# mediaV3_0.net
KiCad netlist of a schematic drawn in Altium Designer
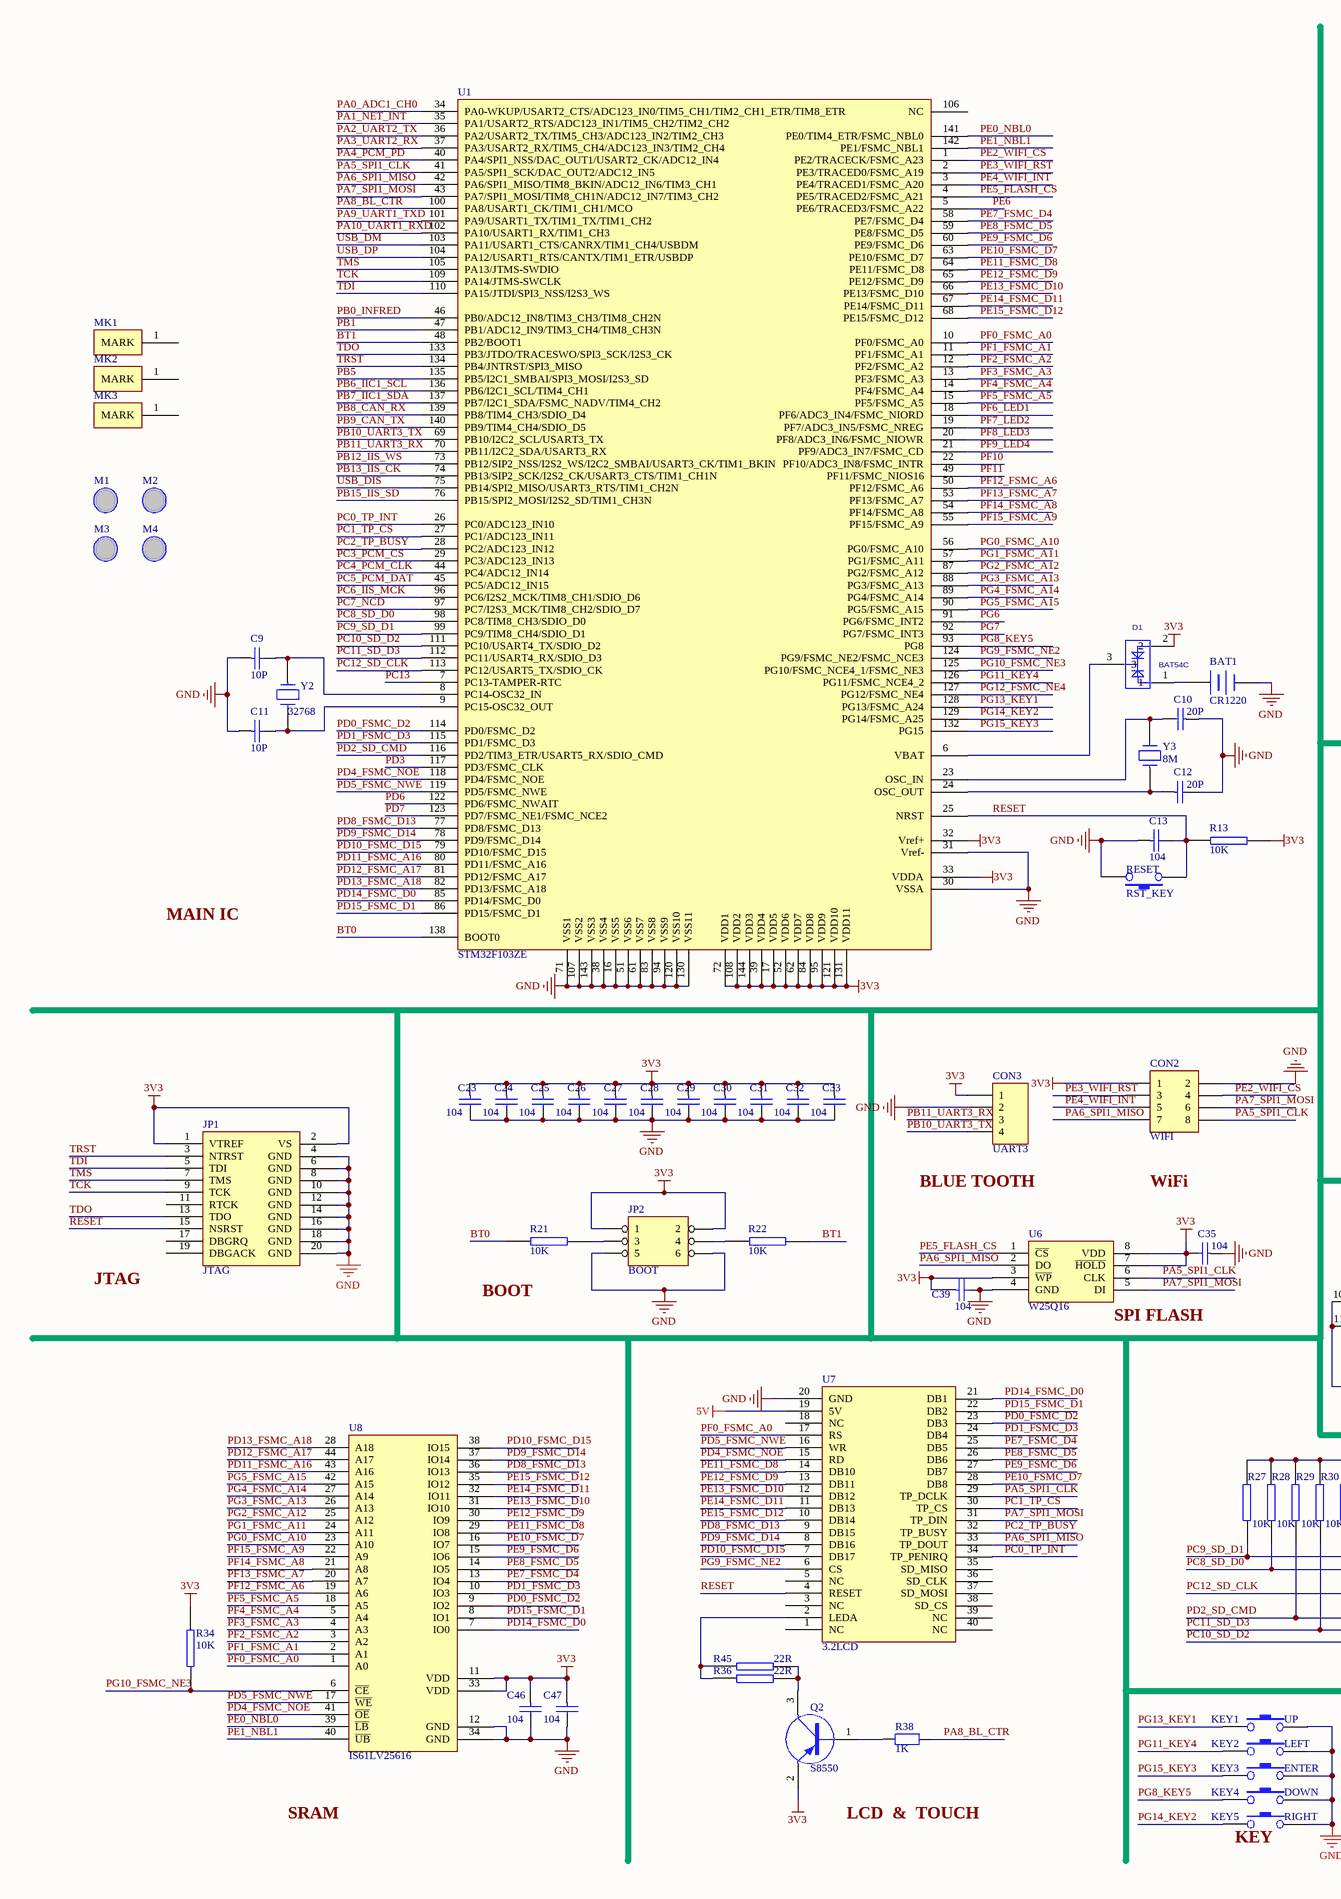
[diagram p0: mediaV3.0.SchDoc, left]
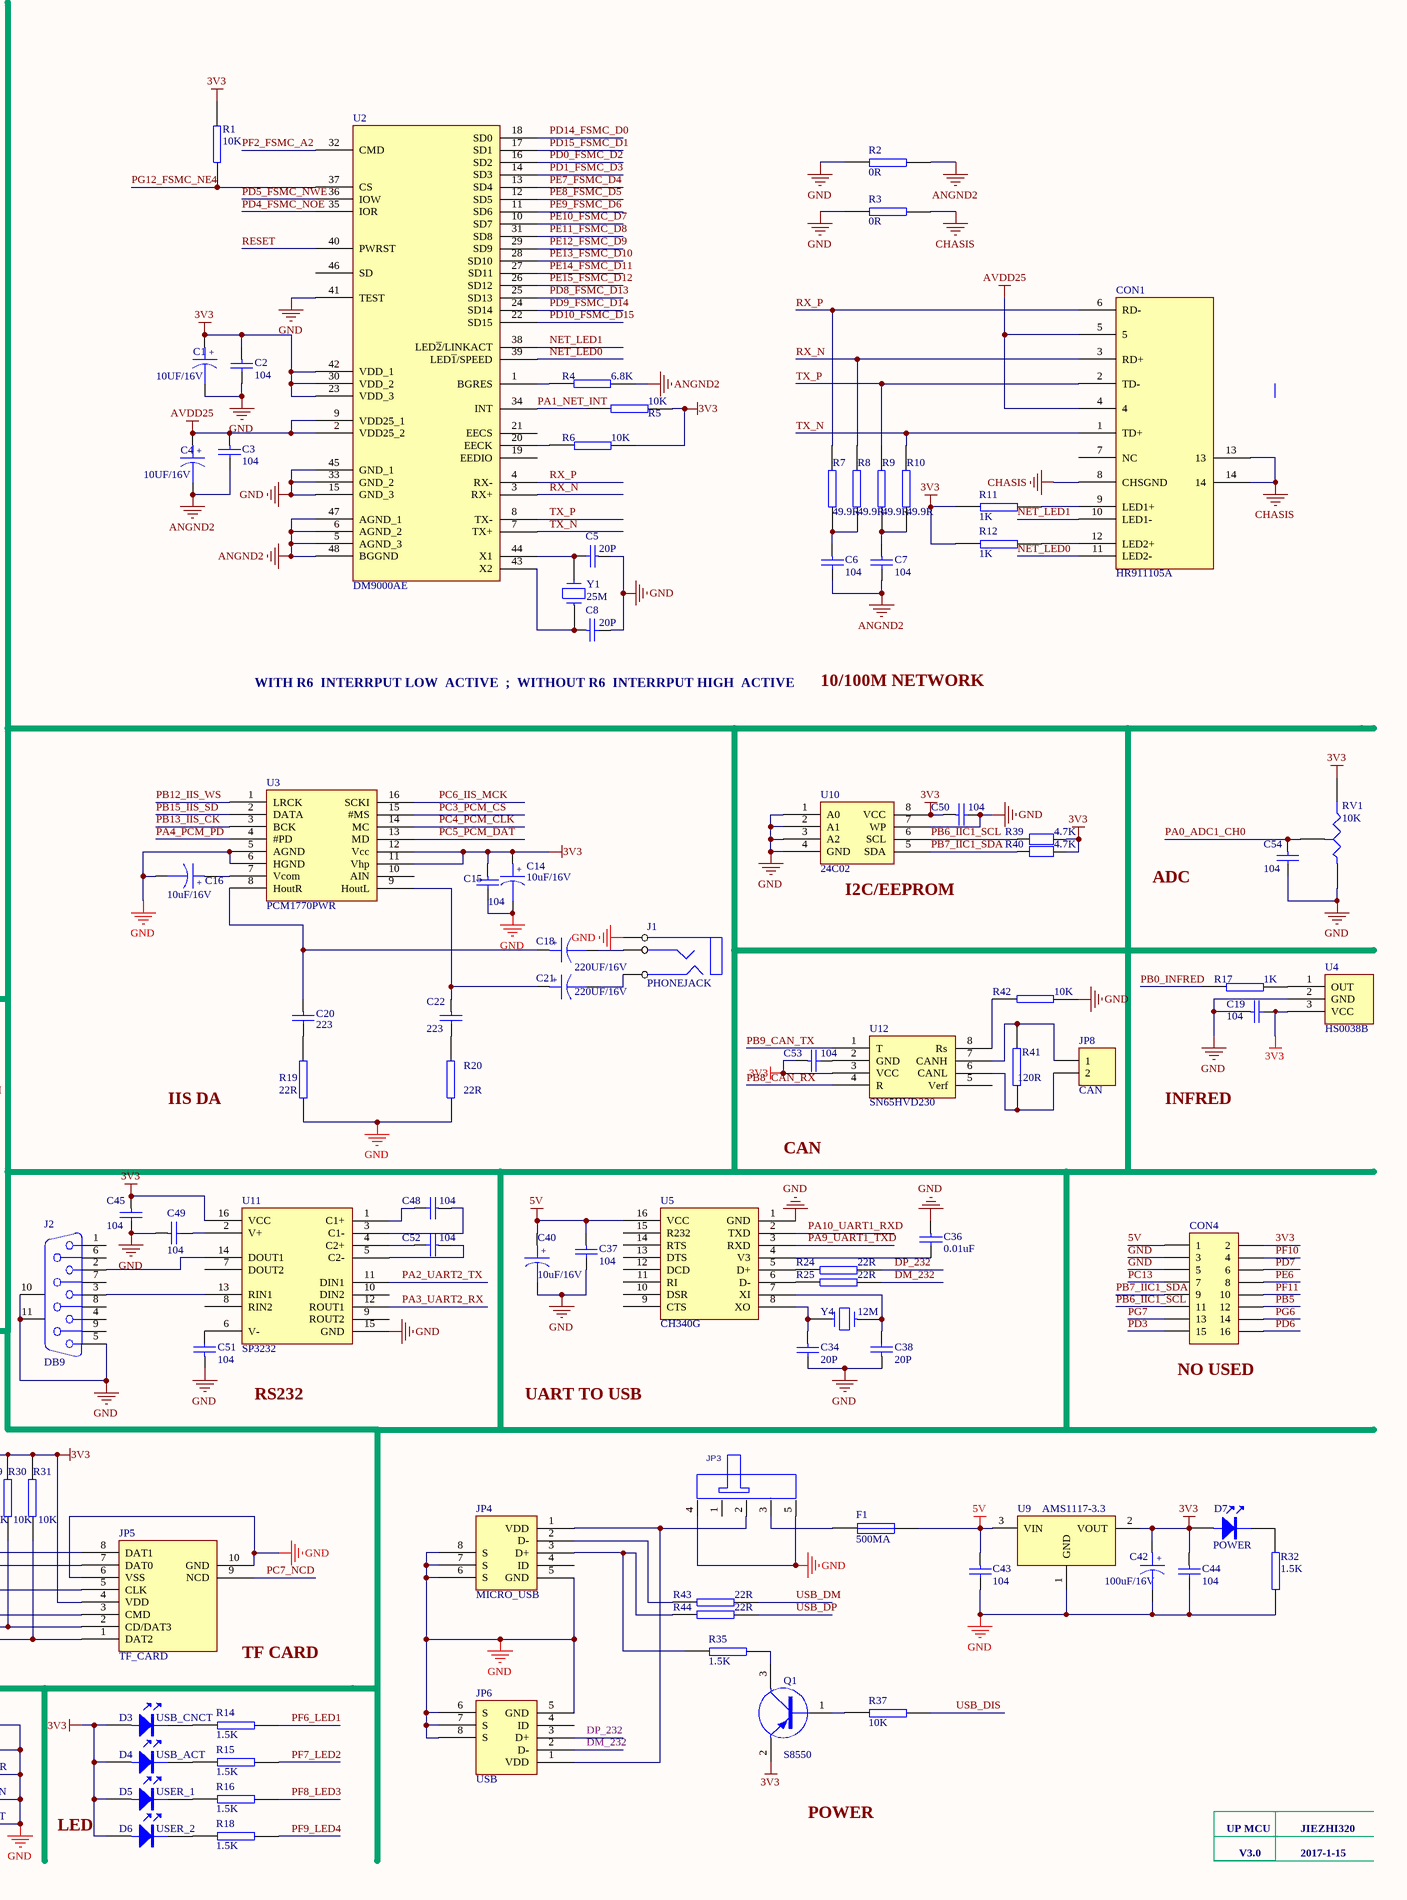
[diagram p1: mediaV3.0.SchDoc, right]

(export (version "E")
  (design (tool "Eeschema 10.0.6"))
  (components
    (comp (ref "BAT1")
      (value "CR1220")
      (footprint "BATM-1220")
      (description "Battery")
      (libsource (lib "Miscellaneous Devices") (part "BATTERY"))
    )
    (comp (ref "C1")
      (value "10UF/16V")
      (footprint "0805C")
      (description "Capacitor")
      (libsource (lib "*") (part "CAPACITOR POL"))
    )
    (comp (ref "C2")
      (value "104")
      (footprint "C0603")
      (description "Capacitor")
      (libsource (lib "*") (part "CAP"))
    )
    (comp (ref "C3")
      (value "104")
      (footprint "C0603")
      (description "Capacitor")
      (libsource (lib "*") (part "CAP"))
    )
    (comp (ref "C4")
      (value "10UF/16V")
      (footprint "0805C")
      (description "Capacitor")
      (libsource (lib "*") (part "CAPACITOR POL"))
    )
    (comp (ref "C5")
      (value "20P")
      (footprint "C0603")
      (description "Capacitor")
      (libsource (lib "*") (part "CAP"))
    )
    (comp (ref "C6")
      (value "104")
      (footprint "C0603")
      (description "Capacitor")
      (libsource (lib "*") (part "CAP"))
    )
    (comp (ref "C7")
      (value "104")
      (footprint "C0603")
      (description "Capacitor")
      (libsource (lib "*") (part "CAP"))
    )
    (comp (ref "C8")
      (value "20P")
      (footprint "C0603")
      (description "Capacitor")
      (libsource (lib "*") (part "CAP"))
    )
    (comp (ref "C9")
      (value "10P")
      (footprint "C0603")
      (description "Capacitor")
      (libsource (lib "*") (part "CAP"))
    )
    (comp (ref "C10")
      (value "20P")
      (footprint "C0603")
      (description "Capacitor")
      (libsource (lib "*") (part "CAP"))
    )
    (comp (ref "C11")
      (value "10P")
      (footprint "C0603")
      (description "Capacitor")
      (libsource (lib "*") (part "CAP"))
    )
    (comp (ref "C12")
      (value "20P")
      (footprint "C0603")
      (description "Capacitor")
      (libsource (lib "*") (part "CAP"))
    )
    (comp (ref "C13")
      (value "104")
      (footprint "C0603")
      (description "Capacitor")
      (libsource (lib "*") (part "CAP"))
    )
    (comp (ref "C14")
      (value "10uF/16V")
      (footprint "0805C")
      (description "Capacitor")
      (libsource (lib "*") (part "CAPACITOR POL"))
    )
    (comp (ref "C15")
      (value "104")
      (footprint "C0603")
      (description "Capacitor")
      (libsource (lib "*") (part "CAP"))
    )
    (comp (ref "C16")
      (value "10uF/16V")
      (footprint "0805C")
      (description "Capacitor")
      (libsource (lib "*") (part "CAPACITOR POL"))
    )
    (comp (ref "C18")
      (value "220UF/16V")
      (footprint "SMD-EC-F6.3")
      (description "Capacitor")
      (libsource (lib "*") (part "CAPACITOR POL"))
    )
    (comp (ref "C19")
      (value "104")
      (footprint "C0603")
      (description "Capacitor")
      (libsource (lib "*") (part "CAP"))
    )
    (comp (ref "C20")
      (value "223")
      (footprint "C0603")
      (description "Capacitor")
      (libsource (lib "*") (part "CAP"))
    )
    (comp (ref "C21")
      (value "220UF/16V")
      (footprint "SMD-EC-F6.3")
      (description "Capacitor")
      (libsource (lib "*") (part "CAPACITOR POL"))
    )
    (comp (ref "C22")
      (value "223")
      (footprint "C0603")
      (description "Capacitor")
      (libsource (lib "*") (part "CAP"))
    )
    (comp (ref "C23")
      (value "104")
      (footprint "C0603")
      (description "Capacitor")
      (libsource (lib "*") (part "CAP"))
    )
    (comp (ref "C24")
      (value "104")
      (footprint "C0603")
      (description "Capacitor")
      (libsource (lib "*") (part "CAP"))
    )
    (comp (ref "C25")
      (value "104")
      (footprint "C0603")
      (description "Capacitor")
      (libsource (lib "*") (part "CAP"))
    )
    (comp (ref "C26")
      (value "104")
      (footprint "C0603")
      (description "Capacitor")
      (libsource (lib "*") (part "CAP"))
    )
    (comp (ref "C27")
      (value "104")
      (footprint "C0603")
      (description "Capacitor")
      (libsource (lib "*") (part "CAP"))
    )
    (comp (ref "C28")
      (value "104")
      (footprint "C0603")
      (description "Capacitor")
      (libsource (lib "*") (part "CAP"))
    )
    (comp (ref "C29")
      (value "104")
      (footprint "C0603")
      (description "Capacitor")
      (libsource (lib "*") (part "CAP"))
    )
    (comp (ref "C30")
      (value "104")
      (footprint "C0603")
      (description "Capacitor")
      (libsource (lib "*") (part "CAP"))
    )
    (comp (ref "C31")
      (value "104")
      (footprint "C0603")
      (description "Capacitor")
      (libsource (lib "*") (part "CAP"))
    )
    (comp (ref "C32")
      (value "104")
      (footprint "C0603")
      (description "Capacitor")
      (libsource (lib "*") (part "CAP"))
    )
    (comp (ref "C33")
      (value "104")
      (footprint "C0603")
      (description "Capacitor")
      (libsource (lib "*") (part "CAP"))
    )
    (comp (ref "C34")
      (value "20P")
      (footprint "C0603")
      (description "Capacitor")
      (libsource (lib "*") (part "CAP"))
    )
    (comp (ref "C35")
      (value "104")
      (footprint "C0603")
      (description "Capacitor")
      (libsource (lib "*") (part "CAP"))
    )
    (comp (ref "C36")
      (value "0.01uF")
      (footprint "C0603")
      (description "Capacitor")
      (libsource (lib "*") (part "CAP"))
    )
    (comp (ref "C37")
      (value "104")
      (footprint "C0603")
      (description "Capacitor")
      (libsource (lib "*") (part "CAP"))
    )
    (comp (ref "C38")
      (value "20P")
      (footprint "C0603")
      (description "Capacitor")
      (libsource (lib "*") (part "CAP"))
    )
    (comp (ref "C39")
      (value "104")
      (footprint "C0603")
      (description "Capacitor")
      (libsource (lib "*") (part "CAP"))
    )
    (comp (ref "C40")
      (value "10uF/16V")
      (footprint "0805C")
      (description "Capacitor")
      (libsource (lib "*") (part "CAPACITOR POL"))
    )
    (comp (ref "C42")
      (value "100uF/16V")
      (footprint "SMD-EC-F6.3")
      (description "Capacitor")
      (libsource (lib "*") (part "CAPACITOR POL"))
    )
    (comp (ref "C43")
      (value "104")
      (footprint "C0603")
      (description "Capacitor")
      (libsource (lib "*") (part "CAP"))
    )
    (comp (ref "C44")
      (value "104")
      (footprint "C0603")
      (description "Capacitor")
      (libsource (lib "*") (part "CAP"))
    )
    (comp (ref "C45")
      (value "104")
      (footprint "C0603")
      (description "Capacitor")
      (libsource (lib "*") (part "CAP"))
    )
    (comp (ref "C46")
      (value "104")
      (footprint "C0603")
      (description "Capacitor")
      (libsource (lib "*") (part "CAP"))
    )
    (comp (ref "C47")
      (value "104")
      (footprint "C0603")
      (description "Capacitor")
      (libsource (lib "*") (part "CAP"))
    )
    (comp (ref "C48")
      (value "104")
      (footprint "C0603")
      (description "Capacitor")
      (libsource (lib "*") (part "CAP"))
    )
    (comp (ref "C49")
      (value "104")
      (footprint "C0603")
      (description "Capacitor")
      (libsource (lib "*") (part "CAP"))
    )
    (comp (ref "C50")
      (value "104")
      (footprint "C0603")
      (description "Capacitor")
      (libsource (lib "*") (part "CAP"))
    )
    (comp (ref "C51")
      (value "104")
      (footprint "C0603")
      (description "Capacitor")
      (libsource (lib "*") (part "CAP"))
    )
    (comp (ref "C52")
      (value "104")
      (footprint "C0603")
      (description "Capacitor")
      (libsource (lib "*") (part "CAP"))
    )
    (comp (ref "C53")
      (value "104")
      (footprint "C0603")
      (description "Capacitor")
      (libsource (lib "*") (part "CAP"))
    )
    (comp (ref "C54")
      (value "104")
      (footprint "C0603")
      (description "Capacitor")
      (libsource (lib "*") (part "CAP"))
    )
    (comp (ref "CON1")
      (value "HR911105A")
      (footprint "CON-HR911105C/RJ45/SC-JL")
      (libsource (lib "*") (part "CN-NET_T/RJ45/HR911105A/HIDE"))
    )
    (comp (ref "CON2")
      (value "WIFI")
      (footprint "WIFI2*4-2.54")
      (description "Header, 4-Pin, Dual row")
      (fields (field (name "PUBLISHER") "Altium Limited"))
      (libsource (lib "Miscellaneous Connectors") (part "Header 4X2"))
    )
    (comp (ref "CON3")
      (value "UART3")
      (footprint "DIP4*1-2.54")
      (description "Header, 4-Pin")
      (fields (field (name "PUBLISHER") "Altium Limited"))
      (libsource (lib "Miscellaneous Connectors") (part "MHDR1X4"))
    )
    (comp (ref "CON4")
      (value "~")
      (footprint "DIP8*2-2.54")
      (description "Header, 8-Pin, Dual row")
      (fields (field (name "PUBLISHER") "Altium Limited"))
      (libsource (lib "Miscellaneous Connectors") (part "Header 8X2"))
    )
    (comp (ref "D1") (value "BAT54C") (footprint "SOT-23") (libsource (lib "F429") (part "BAT54C")))
    (comp (ref "D3")
      (value "USB_CNCT")
      (footprint "D0603")
      (description "POW")
      (libsource (lib "*") (part "LED"))
    )
    (comp (ref "D4") (value "USB_ACT") (footprint "D0603") (libsource (lib "*") (part "LED")))
    (comp (ref "D5") (value "USER_1") (footprint "D0603") (libsource (lib "*") (part "LED")))
    (comp (ref "D6") (value "USER_2") (footprint "D0603") (libsource (lib "*") (part "LED")))
    (comp (ref "D7")
      (value "POWER")
      (footprint "D0603")
      (description "POW")
      (libsource (lib "*") (part "LED"))
    )
    (comp (ref "F1")
      (value "500MA")
      (footprint "R0805")
      (description "Fuse")
      (fields (field (name "PUBLISHER") "Altium Limited"))
      (libsource (lib "Miscellaneous Devices") (part "Fuse 1"))
    )
    (comp (ref "J1")
      (value "PHONEJACK")
      (footprint "PHONE_ST")
      (libsource (lib "*") (part "PHONEJACK STEREO"))
    )
    (comp (ref "J2")
      (value "DB9")
      (footprint "DB-9/FM")
      (description "Receptacle Assembly, 9 Position, Right Angle")
      (fields (field (name "PUBLISHER") "Altium Limited"))
      (libsource (lib "魔笛F4") (part "D Connector 9_Female"))
    )
    (comp (ref "JP1") (value "JTAG") (footprint "JTAG_20") (libsource (lib "*") (part "JTAG")))
    (comp (ref "JP2")
      (value "BOOT")
      (footprint "BOOT_SEL")
      (libsource (lib "Miscellaneous Devices") (part "HEADER 3X2"))
    )
    (comp (ref "JP3")
      (value "SW-POWER")
      (footprint "SW13_6")
      (description "SW-5")
      (libsource (lib "F429") (part "SW-POWER"))
    )
    (comp (ref "JP4")
      (value "MICRO_USB")
      (footprint "USB-MICRO-5P-2 - NJ")
      (libsource (lib "mediaV3.0") (part "MICRO_USB"))
    )
    (comp (ref "JP5") (value "TF_CARD") (footprint "TF-2") (libsource (lib "up-player") (part "TF_CARD")))
    (comp (ref "JP6")
      (value "USB")
      (footprint "USB-MICRO-5P-2 - NJ")
      (libsource (lib "") (part "MICRO_USB_1"))
    )
    (comp (ref "JP8")
      (value "CAN")
      (footprint "CON_2PIN - N")
      (description "Header, 2-Pin")
      (fields (field (name "PUBLISHER") "Altium Limited"))
      (libsource (lib "Miscellaneous Connectors") (part "Header 2"))
    )
    (comp (ref "KEY1") (value "UP") (footprint "KEY4 - SMD") (libsource (lib "*") (part "SW-PB")))
    (comp (ref "KEY2") (value "LEFT") (footprint "KEY4 - SMD") (libsource (lib "*") (part "SW-PB")))
    (comp (ref "KEY3") (value "ENTER") (footprint "KEY4 - SMD") (libsource (lib "*") (part "SW-PB")))
    (comp (ref "KEY4") (value "DOWN") (footprint "KEY4 - SMD") (libsource (lib "*") (part "SW-PB")))
    (comp (ref "KEY5") (value "RIGHT") (footprint "KEY4 - SMD") (libsource (lib "*") (part "SW-PB")))
    (comp (ref "M1") (value "MM") (footprint "PAD") (libsource (lib "mediaV2.1") (part "MM")))
    (comp (ref "M2") (value "MM") (footprint "PAD") (libsource (lib "mediaV2.1") (part "MM")))
    (comp (ref "M3") (value "MM") (footprint "PAD") (libsource (lib "mediaV2.1") (part "MM")))
    (comp (ref "M4") (value "MM") (footprint "PAD") (libsource (lib "mediaV2.1") (part "MM")))
    (comp (ref "MK1") (value "~") (footprint "MARK") (libsource (lib "kevin") (part "MARK")))
    (comp (ref "MK2") (value "~") (footprint "MARK") (libsource (lib "kevin") (part "MARK")))
    (comp (ref "MK3") (value "~") (footprint "MARK") (libsource (lib "kevin") (part "MARK")))
    (comp (ref "Q1")
      (value "S8550")
      (footprint "SOT-23")
      (description "PNP Transistor")
      (libsource (lib "mediaV3.0") (part "PNP"))
    )
    (comp (ref "Q2")
      (value "S8550")
      (footprint "SOT-23")
      (description "PNP Transistor")
      (libsource (lib "mediaV3.0") (part "PNP"))
    )
    (comp (ref "R1") (value "10K") (footprint "R0603") (libsource (lib "*") (part "RES2")))
    (comp (ref "R2") (value "0R") (footprint "R0603") (libsource (lib "*") (part "RES2")))
    (comp (ref "R3") (value "0R") (footprint "R0603") (libsource (lib "*") (part "RES2")))
    (comp (ref "R4") (value "6.8K") (footprint "R0603") (libsource (lib "*") (part "RES2")))
    (comp (ref "R5") (value "10K") (footprint "R0603") (libsource (lib "*") (part "RES2")))
    (comp (ref "R6") (value "10K") (footprint "R0603") (libsource (lib "*") (part "RES2")))
    (comp (ref "R7") (value "49.9R") (footprint "R0603") (libsource (lib "*") (part "RES2")))
    (comp (ref "R8") (value "49.9R") (footprint "R0603") (libsource (lib "*") (part "RES2")))
    (comp (ref "R9") (value "49.9R") (footprint "R0603") (libsource (lib "*") (part "RES2")))
    (comp (ref "R10") (value "49.9R") (footprint "R0603") (libsource (lib "*") (part "RES2")))
    (comp (ref "R11") (value "1K") (footprint "R0603") (libsource (lib "*") (part "RES2")))
    (comp (ref "R12") (value "1K") (footprint "R0603") (libsource (lib "*") (part "RES2")))
    (comp (ref "R13") (value "10K") (footprint "R0603") (libsource (lib "*") (part "RES2")))
    (comp (ref "R14") (value "1.5K") (footprint "R0603") (libsource (lib "*") (part "RES2")))
    (comp (ref "R15") (value "1.5K") (footprint "R0603") (libsource (lib "*") (part "RES2")))
    (comp (ref "R16") (value "1.5K") (footprint "R0603") (libsource (lib "*") (part "RES2")))
    (comp (ref "R17") (value "1K") (footprint "R0603") (libsource (lib "*") (part "RES2")))
    (comp (ref "R18") (value "1.5K") (footprint "R0603") (libsource (lib "*") (part "RES2")))
    (comp (ref "R19") (value "22R") (footprint "R0603") (libsource (lib "*") (part "RES2")))
    (comp (ref "R20") (value "22R") (footprint "R0603") (libsource (lib "*") (part "RES2")))
    (comp (ref "R21") (value "10K") (footprint "R0603") (libsource (lib "*") (part "RES2")))
    (comp (ref "R22") (value "10K") (footprint "R0603") (libsource (lib "*") (part "RES2")))
    (comp (ref "R24") (value "22R") (footprint "R0603") (libsource (lib "*") (part "RES2")))
    (comp (ref "R25") (value "22R") (footprint "R0603") (libsource (lib "*") (part "RES2")))
    (comp (ref "R27") (value "10K") (footprint "R0603") (libsource (lib "*") (part "RES2")))
    (comp (ref "R28") (value "10K") (footprint "R0603") (libsource (lib "*") (part "RES2")))
    (comp (ref "R29") (value "10K") (footprint "R0603") (libsource (lib "*") (part "RES2")))
    (comp (ref "R30") (value "10K") (footprint "R0603") (libsource (lib "*") (part "RES2")))
    (comp (ref "R31") (value "10K") (footprint "R0603") (libsource (lib "*") (part "RES2")))
    (comp (ref "R32") (value "1.5K") (footprint "R0603") (libsource (lib "*") (part "RES2")))
    (comp (ref "R34") (value "10K") (footprint "R0603") (libsource (lib "*") (part "RES2")))
    (comp (ref "R35")
      (value "1.5K")
      (footprint "R0603")
      (libsource (lib "Miscellaneous Devices") (part "RES2"))
    )
    (comp (ref "R36") (value "22R") (footprint "R0603") (libsource (lib "*") (part "RES2")))
    (comp (ref "R37")
      (value "10K")
      (footprint "R0603")
      (libsource (lib "Miscellaneous Devices") (part "RES2"))
    )
    (comp (ref "R38")
      (value "1K")
      (footprint "R0603")
      (description "Resistor")
      (fields (field (name "PUBLISHER") "Altium Limited"))
      (libsource (lib "Miscellaneous Devices") (part "Res2"))
    )
    (comp (ref "R39")
      (value "4.7K")
      (footprint "R0603")
      (description "Resistor")
      (fields (field (name "PUBLISHER") "Altium Limited"))
      (libsource (lib "Miscellaneous Devices") (part "Res2"))
    )
    (comp (ref "R40")
      (value "4.7K")
      (footprint "R0603")
      (description "Resistor")
      (fields (field (name "PUBLISHER") "Altium Limited"))
      (libsource (lib "Miscellaneous Devices") (part "Res2"))
    )
    (comp (ref "R41") (value "120R") (footprint "R0603") (libsource (lib "*") (part "RES2")))
    (comp (ref "R42") (value "10K") (footprint "R0603") (libsource (lib "*") (part "RES2")))
    (comp (ref "R43") (value "22R") (footprint "R0603") (libsource (lib "*") (part "RES2")))
    (comp (ref "R44") (value "22R") (footprint "R0603") (libsource (lib "*") (part "RES2")))
    (comp (ref "R45") (value "22R") (footprint "R0603") (libsource (lib "*") (part "RES2")))
    (comp (ref "RESET") (value "RST_KEY") (footprint "KEY4 - SMD") (libsource (lib "*") (part "SW-PB")))
    (comp (ref "RV1")
      (value "10K")
      (footprint "VR5 - N")
      (libsource (lib "Miscellaneous Devices") (part "RESISTOR TAPPED"))
    )
    (comp (ref "U1")
      (value "STM32F103ZE")
      (footprint "LQFP144-M")
      (libsource (lib "new") (part "STM32F103ZE"))
    )
    (comp (ref "U2")
      (value "DM9000AE")
      (footprint "QFP48")
      (libsource (lib "*") (part "U-DM9000AE/LQFP-48P-Y"))
    )
    (comp (ref "U3") (value "PCM1770PWR") (footprint "TSSOP-16") (libsource (lib "*") (part "PCM1770")))
    (comp (ref "U4") (value "HS0038B") (footprint "HS0038") (libsource (lib "new") (part "INFRED")))
    (comp (ref "U5") (value "CH340G") (footprint "SOP16M") (libsource (lib "Schlib1") (part "CH340G")))
    (comp (ref "U6") (value "W25Q16") (footprint "SOP8") (libsource (lib "mediaV2.1") (part "W25Q16")))
    (comp (ref "U7") (value "3.2LCD") (footprint "LCD") (libsource (lib "media") (part "3.2LCD")))
    (comp (ref "U8") (value "IS61LV25616") (footprint "TSOP44-2") (libsource (lib "*") (part "IS61LV51216")))
    (comp (ref "U9") (value "AMS1117-3.3") (footprint "SOT-223/P2.3") (libsource (lib "*") (part "AMS1117")))
    (comp (ref "U10") (value "24C02") (footprint "SOP-8") (libsource (lib "Schlib1") (part "24C02")))
    (comp (ref "U11") (value "SP3232") (footprint "SOP16M") (libsource (lib "F4") (part "SP3232")))
    (comp (ref "U12")
      (value "SN65HVD230")
      (footprint "SOP-8")
      (libsource (lib "mediaV3.0") (part "SN65HVD230"))
    )
    (comp (ref "Y1")
      (value "25M")
      (footprint "XTAL2")
      (description "Crystal")
      (libsource (lib "*") (part "CRYSTAL"))
    )
    (comp (ref "Y2")
      (value "32768")
      (footprint "XT-32768T")
      (description "Crystal")
      (libsource (lib "*") (part "CRYSTAL"))
    )
    (comp (ref "Y3")
      (value "8M")
      (footprint "XTAL2")
      (description "Crystal")
      (libsource (lib "*") (part "CRYSTAL"))
    )
    (comp (ref "Y4")
      (value "12M")
      (footprint "XTAL2")
      (description "Crystal")
      (libsource (lib "*") (part "CRYSTAL"))
    )
  )
  (nets
    (net (code "2") (name "/BT0") (class "Default")
      (node (ref "R21") (pin "1") (pinfunction "1_1") (pintype "passive"))
      (node (ref "U1") (pin "138") (pinfunction "BOOT0_138") (pintype "passive"))
    )
    (net (code "3") (name "/BT1") (class "Default")
      (node (ref "R22") (pin "2") (pinfunction "2_2") (pintype "passive"))
      (node (ref "U1") (pin "48") (pinfunction "PB2/BOOT1_48") (pintype "passive"))
    )
    (net (code "4") (name "/DM_232") (class "Default")
      (node (ref "JP6") (pin "2") (pinfunction "D-_2") (pintype "passive"))
      (node (ref "R25") (pin "2") (pinfunction "2_2") (pintype "passive"))
    )
    (net (code "5") (name "/DP_232") (class "Default")
      (node (ref "JP6") (pin "3") (pinfunction "D+_3") (pintype "passive"))
      (node (ref "R24") (pin "2") (pinfunction "2_2") (pintype "passive"))
    )
    (net (code "6") (name "/NET_LED0") (class "Default")
      (node (ref "CON1") (pin "11") (pinfunction "LED2-_11") (pintype "passive"))
      (node (ref "U2") (pin "39") (pinfunction "LED~{1}/SPEED_39") (pintype "passive"))
    )
    (net (code "7") (name "/NET_LED1") (class "Default")
      (node (ref "CON1") (pin "10") (pinfunction "LED1-_10") (pintype "passive"))
      (node (ref "U2") (pin "38") (pinfunction "LED~{2}/LINKACT_38") (pintype "passive"))
    )
    (net (code "8") (name "/PA0_ADC1_CH0") (class "Default")
      (node (ref "C54") (pin "1") (pinfunction "1_1") (pintype "passive"))
      (node (ref "RV1") (pin "3") (pinfunction "TAP_3") (pintype "passive"))
      (node (ref "U1") (pin "34") (pinfunction "PA0-WKUP/USART2_CTS/ADC123_IN0/TIM5_CH1/TIM2_CH1_ETR/TIM8_ETR_34") (pintype "passive"))
    )
    (net (code "9") (name "/PA1_NET_INT") (class "Default")
      (node (ref "R5") (pin "1") (pinfunction "1_1") (pintype "passive"))
      (node (ref "U1") (pin "35") (pinfunction "PA1/USART2_RTS/ADC123_IN1/TIM5_CH2/TIM2_CH2_35") (pintype "passive"))
      (node (ref "U2") (pin "34") (pinfunction "INT_34") (pintype "passive"))
    )
    (net (code "10") (name "/PA2_UART2_TX") (class "Default")
      (node (ref "U1") (pin "36") (pinfunction "PA2/USART2_TX/TIM5_CH3/ADC123_IN2/TIM2_CH3_36") (pintype "passive"))
      (node (ref "U11") (pin "11") (pinfunction "DIN1_11") (pintype "passive"))
    )
    (net (code "11") (name "/PA3_UART2_RX") (class "Default")
      (node (ref "U1") (pin "37") (pinfunction "PA3/USART2_RX/TIM5_CH4/ADC123_IN3/TIM2_CH4_37") (pintype "passive"))
      (node (ref "U11") (pin "12") (pinfunction "ROUT1_12") (pintype "passive"))
    )
    (net (code "12") (name "/PA4_PCM_PD") (class "Default")
      (node (ref "U1") (pin "40") (pinfunction "PA4/SPI1_NSS/DAC_OUT1/USART2_CK/ADC12_IN4_40") (pintype "passive"))
      (node (ref "U3") (pin "4") (pinfunction "#PD_4") (pintype "passive"))
    )
    (net (code "13") (name "/PA5_SPI1_CLK") (class "Default")
      (node (ref "CON2") (pin "8") (pinfunction "8_8") (pintype "passive"))
      (node (ref "U1") (pin "41") (pinfunction "PA5/SPI1_SCK/DAC_OUT2/ADC12_IN5_41") (pintype "passive"))
      (node (ref "U6") (pin "6") (pinfunction "CLK_6") (pintype "passive"))
      (node (ref "U7") (pin "29") (pinfunction "TP_DCLK_29") (pintype "passive"))
    )
    (net (code "14") (name "/PA6_SPI1_MISO") (class "Default")
      (node (ref "CON2") (pin "7") (pinfunction "7_7") (pintype "passive"))
      (node (ref "U1") (pin "42") (pinfunction "PA6/SPI1_MISO/TIM8_BKIN/ADC12_IN6/TIM3_CH1_42") (pintype "passive"))
      (node (ref "U6") (pin "2") (pinfunction "DO_2") (pintype "passive"))
      (node (ref "U7") (pin "33") (pinfunction "TP_DOUT_33") (pintype "passive"))
    )
    (net (code "15") (name "/PA7_SPI1_MOSI") (class "Default")
      (node (ref "CON2") (pin "6") (pinfunction "6_6") (pintype "passive"))
      (node (ref "U1") (pin "43") (pinfunction "PA7/SPI1_MOSI/TIM8_CH1N/ADC12_IN7/TIM3_CH2_43") (pintype "passive"))
      (node (ref "U6") (pin "5") (pinfunction "DI_5") (pintype "passive"))
      (node (ref "U7") (pin "31") (pinfunction "TP_DIN_31") (pintype "passive"))
    )
    (net (code "16") (name "/PA8_BL_CTR") (class "Default")
      (node (ref "R38") (pin "2") (pinfunction "2_2") (pintype "passive"))
      (node (ref "U1") (pin "100") (pinfunction "PA8/USART1_CK/TIM1_CH1/MCO_100") (pintype "passive"))
    )
    (net (code "17") (name "/PA9_UART1_TXD") (class "Default")
      (node (ref "U1") (pin "101") (pinfunction "PA9/USART1_TX/TIM1_TX/TIM1_CH2_101") (pintype "passive"))
      (node (ref "U5") (pin "3") (pinfunction "RXD_3") (pintype "passive"))
    )
    (net (code "18") (name "/PA10_UART1_RXD") (class "Default")
      (node (ref "U1") (pin "102") (pinfunction "PA10/USART1_RX/TIM1_CH3_102") (pintype "passive"))
      (node (ref "U5") (pin "2") (pinfunction "TXD_2") (pintype "passive"))
    )
    (net (code "19") (name "/PB0_INFRED") (class "Default")
      (node (ref "R17") (pin "1") (pinfunction "1_1") (pintype "passive"))
      (node (ref "U1") (pin "46") (pinfunction "PB0/ADC12_IN8/TIM3_CH3/TIM8_CH2N_46") (pintype "passive"))
    )
    (net (code "20") (name "/PB1") (class "Default")
      (node (ref "U1") (pin "47") (pinfunction "PB1/ADC12_IN9/TIM3_CH4/TIM8_CH3N_47") (pintype "passive"))
    )
    (net (code "21") (name "/PB5") (class "Default")
      (node (ref "CON4") (pin "12") (pinfunction "12_12") (pintype "passive"))
      (node (ref "U1") (pin "135") (pinfunction "PB5/I2C1_SMBAI/SPI3_MOSI/I2S3_SD_135") (pintype "passive"))
    )
    (net (code "22") (name "/PB6_IIC1_SCL") (class "Default")
      (node (ref "CON4") (pin "11") (pinfunction "11_11") (pintype "passive"))
      (node (ref "R39") (pin "1") (pinfunction "1_1") (pintype "passive"))
      (node (ref "U1") (pin "136") (pinfunction "PB6/I2C1_SCL/TIM4_CH1_136") (pintype "passive"))
      (node (ref "U10") (pin "6") (pinfunction "SCL_6") (pintype "passive"))
    )
    (net (code "23") (name "/PB7_IIC1_SDA") (class "Default")
      (node (ref "CON4") (pin "9") (pinfunction "9_9") (pintype "passive"))
      (node (ref "R40") (pin "1") (pinfunction "1_1") (pintype "passive"))
      (node (ref "U1") (pin "137") (pinfunction "PB7/I2C1_SDA/FSMC_NADV/TIM4_CH2_137") (pintype "passive"))
      (node (ref "U10") (pin "5") (pinfunction "SDA_5") (pintype "passive"))
    )
    (net (code "24") (name "/PB8_CAN_RX") (class "Default")
      (node (ref "U1") (pin "139") (pinfunction "PB8/TIM4_CH3/SDIO_D4_139") (pintype "passive"))
      (node (ref "U12") (pin "4") (pinfunction "R_4") (pintype "passive"))
    )
    (net (code "25") (name "/PB9_CAN_TX") (class "Default")
      (node (ref "U1") (pin "140") (pinfunction "PB9/TIM4_CH4/SDIO_D5_140") (pintype "passive"))
      (node (ref "U12") (pin "1") (pinfunction "T_1") (pintype "passive"))
    )
    (net (code "26") (name "/PB10_UART3_TX") (class "Default")
      (node (ref "CON3") (pin "4") (pinfunction "4_4") (pintype "passive"))
      (node (ref "U1") (pin "69") (pinfunction "PB10/I2C2_SCL/USART3_TX_69") (pintype "passive"))
    )
    (net (code "27") (name "/PB11_UART3_RX") (class "Default")
      (node (ref "CON3") (pin "3") (pinfunction "3_3") (pintype "passive"))
      (node (ref "U1") (pin "70") (pinfunction "PB11/I2C2_SDA/USART3_RX_70") (pintype "passive"))
    )
    (net (code "28") (name "/PB12_IIS_WS") (class "Default")
      (node (ref "U1") (pin "73") (pinfunction "PB12/SIP2_NSS/I2S2_WS/I2C2_SMBAI/USART3_CK/TIM1_BKIN_73") (pintype "passive"))
      (node (ref "U3") (pin "1") (pinfunction "LRCK_1") (pintype "passive"))
    )
    (net (code "29") (name "/PB13_IIS_CK") (class "Default")
      (node (ref "U1") (pin "74") (pinfunction "PB13/SIP2_SCK/I2S2_CK/USART3_CTS/TIM1_CH1N_74") (pintype "passive"))
      (node (ref "U3") (pin "3") (pinfunction "BCK_3") (pintype "passive"))
    )
    (net (code "30") (name "/PB15_IIS_SD") (class "Default")
      (node (ref "U1") (pin "76") (pinfunction "PB15/SPI2_MOSI/I2S2_SD/TIM1_CH3N_76") (pintype "passive"))
      (node (ref "U3") (pin "2") (pinfunction "DATA_2") (pintype "passive"))
    )
    (net (code "31") (name "/PC0_TP_INT") (class "Default")
      (node (ref "U1") (pin "26") (pinfunction "PC0/ADC123_IN10_26") (pintype "passive"))
      (node (ref "U7") (pin "34") (pinfunction "TP_PENIRQ_34") (pintype "passive"))
    )
    (net (code "32") (name "/PC1_TP_CS") (class "Default")
      (node (ref "U1") (pin "27") (pinfunction "PC1/ADC123_IN11_27") (pintype "passive"))
      (node (ref "U7") (pin "30") (pinfunction "TP_CS_30") (pintype "passive"))
    )
    (net (code "33") (name "/PC2_TP_BUSY") (class "Default")
      (node (ref "U1") (pin "28") (pinfunction "PC2/ADC123_IN12_28") (pintype "passive"))
      (node (ref "U7") (pin "32") (pinfunction "TP_BUSY_32") (pintype "passive"))
    )
    (net (code "34") (name "/PC3_PCM_CS") (class "Default")
      (node (ref "U1") (pin "29") (pinfunction "PC3/ADC123_IN13_29") (pintype "passive"))
      (node (ref "U3") (pin "15") (pinfunction "#MS_15") (pintype "passive"))
    )
    (net (code "35") (name "/PC4_PCM_CLK") (class "Default")
      (node (ref "U1") (pin "44") (pinfunction "PC4/ADC12_IN14_44") (pintype "passive"))
      (node (ref "U3") (pin "14") (pinfunction "MC_14") (pintype "passive"))
    )
    (net (code "36") (name "/PC5_PCM_DAT") (class "Default")
      (node (ref "U1") (pin "45") (pinfunction "PC5/ADC12_IN15_45") (pintype "passive"))
      (node (ref "U3") (pin "13") (pinfunction "MD_13") (pintype "passive"))
    )
    (net (code "37") (name "/PC6_IIS_MCK") (class "Default")
      (node (ref "U1") (pin "96") (pinfunction "PC6/I2S2_MCK/TIM8_CH1/SDIO_D6_96") (pintype "passive"))
      (node (ref "U3") (pin "16") (pinfunction "SCKI_16") (pintype "passive"))
    )
    (net (code "38") (name "/PC7_NCD") (class "Default")
      (node (ref "JP5") (pin "9") (pinfunction "NCD_9") (pintype "passive"))
      (node (ref "U1") (pin "97") (pinfunction "PC7/I2S3_MCK/TIM8_CH2/SDIO_D7_97") (pintype "passive"))
    )
    (net (code "39") (name "/PC8_SD_D0") (class "Default")
      (node (ref "JP5") (pin "7") (pinfunction "DAT0_7") (pintype "passive"))
      (node (ref "R28") (pin "1") (pinfunction "1_1") (pintype "passive"))
      (node (ref "U1") (pin "98") (pinfunction "PC8/TIM8_CH3/SDIO_D0_98") (pintype "passive"))
    )
    (net (code "40") (name "/PC9_SD_D1") (class "Default")
      (node (ref "JP5") (pin "8") (pinfunction "DAT1_8") (pintype "passive"))
      (node (ref "R27") (pin "1") (pinfunction "1_1") (pintype "passive"))
      (node (ref "U1") (pin "99") (pinfunction "PC9/TIM8_CH4/SDIO_D1_99") (pintype "passive"))
    )
    (net (code "41") (name "/PC10_SD_D2") (class "Default")
      (node (ref "JP5") (pin "1") (pinfunction "DAT2_1") (pintype "passive"))
      (node (ref "R31") (pin "1") (pinfunction "1_1") (pintype "passive"))
      (node (ref "U1") (pin "111") (pinfunction "PC10/USART4_TX/SDIO_D2_111") (pintype "passive"))
    )
    (net (code "42") (name "/PC11_SD_D3") (class "Default")
      (node (ref "JP5") (pin "2") (pinfunction "CD/DAT3_2") (pintype "passive"))
      (node (ref "R30") (pin "1") (pinfunction "1_1") (pintype "passive"))
      (node (ref "U1") (pin "112") (pinfunction "PC11/USART4_RX/SDIO_D3_112") (pintype "passive"))
    )
    (net (code "43") (name "/PC12_SD_CLK") (class "Default")
      (node (ref "JP5") (pin "5") (pinfunction "CLK_5") (pintype "passive"))
      (node (ref "U1") (pin "113") (pinfunction "PC12/USART5_TX/SDIO_CK_113") (pintype "passive"))
    )
    (net (code "44") (name "/PC13") (class "Default")
      (node (ref "CON4") (pin "7") (pinfunction "7_7") (pintype "passive"))
      (node (ref "U1") (pin "7") (pinfunction "PC13-TAMPER-RTC_7") (pintype "passive"))
    )
    (net (code "45") (name "/PD0_FSMC_D2") (class "Default")
      (node (ref "U1") (pin "114") (pinfunction "PD0/FSMC_D2_114") (pintype "passive"))
      (node (ref "U2") (pin "16") (pinfunction "SD2_16") (pintype "passive"))
      (node (ref "U7") (pin "23") (pinfunction "DB3_23") (pintype "passive"))
      (node (ref "U8") (pin "9") (pinfunction "IO2_9") (pintype "passive"))
    )
    (net (code "46") (name "/PD1_FSMC_D3") (class "Default")
      (node (ref "U1") (pin "115") (pinfunction "PD1/FSMC_D3_115") (pintype "passive"))
      (node (ref "U2") (pin "14") (pinfunction "SD3_14") (pintype "passive"))
      (node (ref "U7") (pin "24") (pinfunction "DB4_24") (pintype "passive"))
      (node (ref "U8") (pin "10") (pinfunction "IO3_10") (pintype "passive"))
    )
    (net (code "47") (name "/PD2_SD_CMD") (class "Default")
      (node (ref "JP5") (pin "3") (pinfunction "CMD_3") (pintype "passive"))
      (node (ref "R29") (pin "1") (pinfunction "1_1") (pintype "passive"))
      (node (ref "U1") (pin "116") (pinfunction "PD2/TIM3_ETR/USART5_RX/SDIO_CMD_116") (pintype "passive"))
    )
    (net (code "48") (name "/PD3") (class "Default")
      (node (ref "CON4") (pin "15") (pinfunction "15_15") (pintype "passive"))
      (node (ref "U1") (pin "117") (pinfunction "PD3/FSMC_CLK_117") (pintype "passive"))
    )
    (net (code "49") (name "/PD4_FSMC_NOE") (class "Default")
      (node (ref "U1") (pin "118") (pinfunction "PD4/FSMC_NOE_118") (pintype "passive"))
      (node (ref "U2") (pin "35") (pinfunction "IOR_35") (pintype "passive"))
      (node (ref "U7") (pin "15") (pinfunction "RD_15") (pintype "passive"))
      (node (ref "U8") (pin "41") (pinfunction "~{OE}_41") (pintype "passive"))
    )
    (net (code "50") (name "/PD5_FSMC_NWE") (class "Default")
      (node (ref "U1") (pin "119") (pinfunction "PD5/FSMC_NWE_119") (pintype "passive"))
      (node (ref "U2") (pin "36") (pinfunction "IOW_36") (pintype "passive"))
      (node (ref "U7") (pin "16") (pinfunction "WR_16") (pintype "passive"))
      (node (ref "U8") (pin "17") (pinfunction "~{WE}_17") (pintype "passive"))
    )
    (net (code "51") (name "/PD6") (class "Default")
      (node (ref "CON4") (pin "16") (pinfunction "16_16") (pintype "passive"))
      (node (ref "U1") (pin "122") (pinfunction "PD6/FSMC_NWAIT_122") (pintype "passive"))
    )
    (net (code "52") (name "/PD7") (class "Default")
      (node (ref "CON4") (pin "6") (pinfunction "6_6") (pintype "passive"))
      (node (ref "U1") (pin "123") (pinfunction "PD7/FSMC_NE1/FSMC_NCE2_123") (pintype "passive"))
    )
    (net (code "53") (name "/PD8_FSMC_D13") (class "Default")
      (node (ref "U1") (pin "77") (pinfunction "PD8/FSMC_D13_77") (pintype "passive"))
      (node (ref "U2") (pin "25") (pinfunction "SD13_25") (pintype "passive"))
      (node (ref "U7") (pin "9") (pinfunction "DB15_9") (pintype "passive"))
      (node (ref "U8") (pin "36") (pinfunction "IO13_36") (pintype "passive"))
    )
    (net (code "54") (name "/PD9_FSMC_D14") (class "Default")
      (node (ref "U1") (pin "78") (pinfunction "PD9/FSMC_D14_78") (pintype "passive"))
      (node (ref "U2") (pin "24") (pinfunction "SD14_24") (pintype "passive"))
      (node (ref "U7") (pin "8") (pinfunction "DB16_8") (pintype "passive"))
      (node (ref "U8") (pin "37") (pinfunction "IO14_37") (pintype "passive"))
    )
    (net (code "55") (name "/PD10_FSMC_D15") (class "Default")
      (node (ref "U1") (pin "79") (pinfunction "PD10/FSMC_D15_79") (pintype "passive"))
      (node (ref "U2") (pin "22") (pinfunction "SD15_22") (pintype "passive"))
      (node (ref "U7") (pin "7") (pinfunction "DB17_7") (pintype "passive"))
      (node (ref "U8") (pin "38") (pinfunction "IO15_38") (pintype "passive"))
    )
    (net (code "56") (name "/PD11_FSMC_A16") (class "Default")
      (node (ref "U1") (pin "80") (pinfunction "PD11/FSMC_A16_80") (pintype "passive"))
      (node (ref "U8") (pin "43") (pinfunction "A16_43") (pintype "passive"))
    )
    (net (code "57") (name "/PD12_FSMC_A17") (class "Default")
      (node (ref "U1") (pin "81") (pinfunction "PD12/FSMC_A17_81") (pintype "passive"))
      (node (ref "U8") (pin "44") (pinfunction "A17_44") (pintype "passive"))
    )
    (net (code "58") (name "/PD13_FSMC_A18") (class "Default")
      (node (ref "U1") (pin "82") (pinfunction "PD13/FSMC_A18_82") (pintype "passive"))
      (node (ref "U8") (pin "28") (pinfunction "A18_28") (pintype "passive"))
    )
    (net (code "59") (name "/PD14_FSMC_D0") (class "Default")
      (node (ref "U1") (pin "85") (pinfunction "PD14/FSMC_D0_85") (pintype "passive"))
      (node (ref "U2") (pin "18") (pinfunction "SD0_18") (pintype "passive"))
      (node (ref "U7") (pin "21") (pinfunction "DB1_21") (pintype "passive"))
      (node (ref "U8") (pin "7") (pinfunction "IO0_7") (pintype "passive"))
    )
    (net (code "60") (name "/PD15_FSMC_D1") (class "Default")
      (node (ref "U1") (pin "86") (pinfunction "PD15/FSMC_D1_86") (pintype "passive"))
      (node (ref "U2") (pin "17") (pinfunction "SD1_17") (pintype "passive"))
      (node (ref "U7") (pin "22") (pinfunction "DB2_22") (pintype "passive"))
      (node (ref "U8") (pin "8") (pinfunction "IO1_8") (pintype "passive"))
    )
    (net (code "61") (name "/PE0_NBL0") (class "Default")
      (node (ref "U1") (pin "141") (pinfunction "PE0/TIM4_ETR/FSMC_NBL0_141") (pintype "passive"))
      (node (ref "U8") (pin "39") (pinfunction "~{LB}_39") (pintype "passive"))
    )
    (net (code "62") (name "/PE1_NBL1") (class "Default")
      (node (ref "U1") (pin "142") (pinfunction "PE1/FSMC_NBL1_142") (pintype "passive"))
      (node (ref "U8") (pin "40") (pinfunction "~{UB}_40") (pintype "passive"))
    )
    (net (code "63") (name "/PE2_WIFI_CS") (class "Default")
      (node (ref "CON2") (pin "4") (pinfunction "4_4") (pintype "passive"))
      (node (ref "U1") (pin "1") (pinfunction "PE2/TRACECK/FSMC_A23_1") (pintype "passive"))
    )
    (net (code "64") (name "/PE3_WIFI_RST") (class "Default")
      (node (ref "CON2") (pin "3") (pinfunction "3_3") (pintype "passive"))
      (node (ref "U1") (pin "2") (pinfunction "PE3/TRACED0/FSMC_A19_2") (pintype "passive"))
    )
    (net (code "65") (name "/PE4_WIFI_INT") (class "Default")
      (node (ref "CON2") (pin "5") (pinfunction "5_5") (pintype "passive"))
      (node (ref "U1") (pin "3") (pinfunction "PE4/TRACED1/FSMC_A20_3") (pintype "passive"))
    )
    (net (code "66") (name "/PE5_FLASH_CS") (class "Default")
      (node (ref "U1") (pin "4") (pinfunction "PE5/TRACED2/FSMC_A21_4") (pintype "passive"))
      (node (ref "U6") (pin "1") (pinfunction "~{CS}_1") (pintype "passive"))
    )
    (net (code "67") (name "/PE6") (class "Default")
      (node (ref "CON4") (pin "8") (pinfunction "8_8") (pintype "passive"))
      (node (ref "U1") (pin "5") (pinfunction "PE6/TRACED3/FSMC_A22_5") (pintype "passive"))
    )
    (net (code "68") (name "/PE7_FSMC_D4") (class "Default")
      (node (ref "U1") (pin "58") (pinfunction "PE7/FSMC_D4_58") (pintype "passive"))
      (node (ref "U2") (pin "13") (pinfunction "SD4_13") (pintype "passive"))
      (node (ref "U7") (pin "25") (pinfunction "DB5_25") (pintype "passive"))
      (node (ref "U8") (pin "13") (pinfunction "IO4_13") (pintype "passive"))
    )
    (net (code "69") (name "/PE8_FSMC_D5") (class "Default")
      (node (ref "U1") (pin "59") (pinfunction "PE8/FSMC_D5_59") (pintype "passive"))
      (node (ref "U2") (pin "12") (pinfunction "SD5_12") (pintype "passive"))
      (node (ref "U7") (pin "26") (pinfunction "DB6_26") (pintype "passive"))
      (node (ref "U8") (pin "14") (pinfunction "IO5_14") (pintype "passive"))
    )
    (net (code "70") (name "/PE9_FSMC_D6") (class "Default")
      (node (ref "U1") (pin "60") (pinfunction "PE9/FSMC_D6_60") (pintype "passive"))
      (node (ref "U2") (pin "11") (pinfunction "SD6_11") (pintype "passive"))
      (node (ref "U7") (pin "27") (pinfunction "DB7_27") (pintype "passive"))
      (node (ref "U8") (pin "15") (pinfunction "IO6_15") (pintype "passive"))
    )
    (net (code "71") (name "/PE10_FSMC_D7") (class "Default")
      (node (ref "U1") (pin "63") (pinfunction "PE10/FSMC_D7_63") (pintype "passive"))
      (node (ref "U2") (pin "10") (pinfunction "SD7_10") (pintype "passive"))
      (node (ref "U7") (pin "28") (pinfunction "DB8_28") (pintype "passive"))
      (node (ref "U8") (pin "16") (pinfunction "IO7_16") (pintype "passive"))
    )
    (net (code "72") (name "/PE11_FSMC_D8") (class "Default")
      (node (ref "U1") (pin "64") (pinfunction "PE11/FSMC_D8_64") (pintype "passive"))
      (node (ref "U2") (pin "31") (pinfunction "SD8_31") (pintype "passive"))
      (node (ref "U7") (pin "14") (pinfunction "DB10_14") (pintype "passive"))
      (node (ref "U8") (pin "29") (pinfunction "IO8_29") (pintype "passive"))
    )
    (net (code "73") (name "/PE12_FSMC_D9") (class "Default")
      (node (ref "U1") (pin "65") (pinfunction "PE12/FSMC_D9_65") (pintype "passive"))
      (node (ref "U2") (pin "29") (pinfunction "SD9_29") (pintype "passive"))
      (node (ref "U7") (pin "13") (pinfunction "DB11_13") (pintype "passive"))
      (node (ref "U8") (pin "30") (pinfunction "IO9_30") (pintype "passive"))
    )
    (net (code "74") (name "/PE13_FSMC_D10") (class "Default")
      (node (ref "U1") (pin "66") (pinfunction "PE13/FSMC_D10_66") (pintype "passive"))
      (node (ref "U2") (pin "28") (pinfunction "SD10_28") (pintype "passive"))
      (node (ref "U7") (pin "12") (pinfunction "DB12_12") (pintype "passive"))
      (node (ref "U8") (pin "31") (pinfunction "IO10_31") (pintype "passive"))
    )
    (net (code "75") (name "/PE14_FSMC_D11") (class "Default")
      (node (ref "U1") (pin "67") (pinfunction "PE14/FSMC_D11_67") (pintype "passive"))
      (node (ref "U2") (pin "27") (pinfunction "SD11_27") (pintype "passive"))
      (node (ref "U7") (pin "11") (pinfunction "DB13_11") (pintype "passive"))
      (node (ref "U8") (pin "32") (pinfunction "IO11_32") (pintype "passive"))
    )
    (net (code "76") (name "/PE15_FSMC_D12") (class "Default")
      (node (ref "U1") (pin "68") (pinfunction "PE15/FSMC_D12_68") (pintype "passive"))
      (node (ref "U2") (pin "26") (pinfunction "SD12_26") (pintype "passive"))
      (node (ref "U7") (pin "10") (pinfunction "DB14_10") (pintype "passive"))
      (node (ref "U8") (pin "35") (pinfunction "IO12_35") (pintype "passive"))
    )
    (net (code "77") (name "/PF0_FSMC_A0") (class "Default")
      (node (ref "U1") (pin "10") (pinfunction "PF0/FSMC_A0_10") (pintype "passive"))
      (node (ref "U7") (pin "17") (pinfunction "RS_17") (pintype "passive"))
      (node (ref "U8") (pin "1") (pinfunction "A0_1") (pintype "passive"))
    )
    (net (code "78") (name "/PF1_FSMC_A1") (class "Default")
      (node (ref "U1") (pin "11") (pinfunction "PF1/FSMC_A1_11") (pintype "passive"))
      (node (ref "U8") (pin "2") (pinfunction "A1_2") (pintype "passive"))
    )
    (net (code "79") (name "/PF2_FSMC_A2") (class "Default")
      (node (ref "U1") (pin "12") (pinfunction "PF2/FSMC_A2_12") (pintype "passive"))
      (node (ref "U2") (pin "32") (pinfunction "CMD_32") (pintype "passive"))
      (node (ref "U8") (pin "3") (pinfunction "A2_3") (pintype "passive"))
    )
    (net (code "80") (name "/PF3_FSMC_A3") (class "Default")
      (node (ref "U1") (pin "13") (pinfunction "PF3/FSMC_A3_13") (pintype "passive"))
      (node (ref "U8") (pin "4") (pinfunction "A3_4") (pintype "passive"))
    )
    (net (code "81") (name "/PF4_FSMC_A4") (class "Default")
      (node (ref "U1") (pin "14") (pinfunction "PF4/FSMC_A4_14") (pintype "passive"))
      (node (ref "U8") (pin "5") (pinfunction "A4_5") (pintype "passive"))
    )
    (net (code "82") (name "/PF5_FSMC_A5") (class "Default")
      (node (ref "U1") (pin "15") (pinfunction "PF5/FSMC_A5_15") (pintype "passive"))
      (node (ref "U8") (pin "18") (pinfunction "A5_18") (pintype "passive"))
    )
    (net (code "83") (name "/PF6_LED1") (class "Default")
      (node (ref "R14") (pin "2") (pinfunction "2_2") (pintype "passive"))
      (node (ref "U1") (pin "18") (pinfunction "PF6/ADC3_IN4/FSMC_NIORD_18") (pintype "passive"))
    )
    (net (code "84") (name "/PF7_LED2") (class "Default")
      (node (ref "R15") (pin "2") (pinfunction "2_2") (pintype "passive"))
      (node (ref "U1") (pin "19") (pinfunction "PF7/ADC3_IN5/FSMC_NREG_19") (pintype "passive"))
    )
    (net (code "85") (name "/PF8_LED3") (class "Default")
      (node (ref "R16") (pin "2") (pinfunction "2_2") (pintype "passive"))
      (node (ref "U1") (pin "20") (pinfunction "PF8/ADC3_IN6/FSMC_NIOWR_20") (pintype "passive"))
    )
    (net (code "86") (name "/PF9_LED4") (class "Default")
      (node (ref "R18") (pin "2") (pinfunction "2_2") (pintype "passive"))
      (node (ref "U1") (pin "21") (pinfunction "PF9/ADC3_IN7/FSMC_CD_21") (pintype "passive"))
    )
    (net (code "87") (name "/PF10") (class "Default")
      (node (ref "CON4") (pin "4") (pinfunction "4_4") (pintype "passive"))
      (node (ref "U1") (pin "22") (pinfunction "PF10/ADC3_IN8/FSMC_INTR_22") (pintype "passive"))
    )
    (net (code "88") (name "/PF11") (class "Default")
      (node (ref "CON4") (pin "10") (pinfunction "10_10") (pintype "passive"))
      (node (ref "U1") (pin "49") (pinfunction "PF11/FSMC_NIOS16_49") (pintype "passive"))
    )
    (net (code "89") (name "/PF12_FSMC_A6") (class "Default")
      (node (ref "U1") (pin "50") (pinfunction "PF12/FSMC_A6_50") (pintype "passive"))
      (node (ref "U8") (pin "19") (pinfunction "A6_19") (pintype "passive"))
    )
    (net (code "90") (name "/PF13_FSMC_A7") (class "Default")
      (node (ref "U1") (pin "53") (pinfunction "PF13/FSMC_A7_53") (pintype "passive"))
      (node (ref "U8") (pin "20") (pinfunction "A7_20") (pintype "passive"))
    )
    (net (code "91") (name "/PF14_FSMC_A8") (class "Default")
      (node (ref "U1") (pin "54") (pinfunction "PF14/FSMC_A8_54") (pintype "passive"))
      (node (ref "U8") (pin "21") (pinfunction "A8_21") (pintype "passive"))
    )
    (net (code "92") (name "/PF15_FSMC_A9") (class "Default")
      (node (ref "U1") (pin "55") (pinfunction "PF15/FSMC_A9_55") (pintype "passive"))
      (node (ref "U8") (pin "22") (pinfunction "A9_22") (pintype "passive"))
    )
    (net (code "93") (name "/PG0_FSMC_A10") (class "Default")
      (node (ref "U1") (pin "56") (pinfunction "PG0/FSMC_A10_56") (pintype "passive"))
      (node (ref "U8") (pin "23") (pinfunction "A10_23") (pintype "passive"))
    )
    (net (code "94") (name "/PG1_FSMC_A11") (class "Default")
      (node (ref "U1") (pin "57") (pinfunction "PG1/FSMC_A11_57") (pintype "passive"))
      (node (ref "U8") (pin "24") (pinfunction "A11_24") (pintype "passive"))
    )
    (net (code "95") (name "/PG2_FSMC_A12") (class "Default")
      (node (ref "U1") (pin "87") (pinfunction "PG2/FSMC_A12_87") (pintype "passive"))
      (node (ref "U8") (pin "25") (pinfunction "A12_25") (pintype "passive"))
    )
    (net (code "96") (name "/PG3_FSMC_A13") (class "Default")
      (node (ref "U1") (pin "88") (pinfunction "PG3/FSMC_A13_88") (pintype "passive"))
      (node (ref "U8") (pin "26") (pinfunction "A13_26") (pintype "passive"))
    )
    (net (code "97") (name "/PG4_FSMC_A14") (class "Default")
      (node (ref "U1") (pin "89") (pinfunction "PG4/FSMC_A14_89") (pintype "passive"))
      (node (ref "U8") (pin "27") (pinfunction "A14_27") (pintype "passive"))
    )
    (net (code "98") (name "/PG5_FSMC_A15") (class "Default")
      (node (ref "U1") (pin "90") (pinfunction "PG5/FSMC_A15_90") (pintype "passive"))
      (node (ref "U8") (pin "42") (pinfunction "A15_42") (pintype "passive"))
    )
    (net (code "99") (name "/PG6") (class "Default")
      (node (ref "CON4") (pin "14") (pinfunction "14_14") (pintype "passive"))
      (node (ref "U1") (pin "91") (pinfunction "PG6/FSMC_INT2_91") (pintype "passive"))
    )
    (net (code "100") (name "/PG7") (class "Default")
      (node (ref "CON4") (pin "13") (pinfunction "13_13") (pintype "passive"))
      (node (ref "U1") (pin "92") (pinfunction "PG7/FSMC_INT3_92") (pintype "passive"))
    )
    (net (code "101") (name "/PG8_KEY5") (class "Default")
      (node (ref "KEY4") (pin "2") (pinfunction "2_2") (pintype "passive"))
      (node (ref "U1") (pin "93") (pinfunction "PG8_93") (pintype "passive"))
    )
    (net (code "102") (name "/PG9_FSMC_NE2") (class "Default")
      (node (ref "U1") (pin "124") (pinfunction "PG9/FSMC_NE2/FSMC_NCE3_124") (pintype "passive"))
      (node (ref "U7") (pin "6") (pinfunction "CS_6") (pintype "passive"))
    )
    (net (code "103") (name "/PG10_FSMC_NE3") (class "Default")
      (node (ref "R34") (pin "1") (pinfunction "1_1") (pintype "passive"))
      (node (ref "U1") (pin "125") (pinfunction "PG10/FSMC_NCE4_1/FSMC_NE3_125") (pintype "passive"))
      (node (ref "U8") (pin "6") (pinfunction "~{CE}_6") (pintype "passive"))
    )
    (net (code "104") (name "/PG11_KEY4") (class "Default")
      (node (ref "KEY2") (pin "2") (pinfunction "2_2") (pintype "passive"))
      (node (ref "U1") (pin "126") (pinfunction "PG11/FSMC_NCE4_2_126") (pintype "passive"))
    )
    (net (code "105") (name "/PG12_FSMC_NE4") (class "Default")
      (node (ref "R1") (pin "1") (pinfunction "1_1") (pintype "passive"))
      (node (ref "U1") (pin "127") (pinfunction "PG12/FSMC_NE4_127") (pintype "passive"))
      (node (ref "U2") (pin "37") (pinfunction "CS_37") (pintype "passive"))
    )
    (net (code "106") (name "/PG13_KEY1") (class "Default")
      (node (ref "KEY1") (pin "2") (pinfunction "2_2") (pintype "passive"))
      (node (ref "U1") (pin "128") (pinfunction "PG13/FSMC_A24_128") (pintype "passive"))
    )
    (net (code "107") (name "/PG14_KEY2") (class "Default")
      (node (ref "KEY5") (pin "2") (pinfunction "2_2") (pintype "passive"))
      (node (ref "U1") (pin "129") (pinfunction "PG14/FSMC_A25_129") (pintype "passive"))
    )
    (net (code "108") (name "/PG15_KEY3") (class "Default")
      (node (ref "KEY3") (pin "2") (pinfunction "2_2") (pintype "passive"))
      (node (ref "U1") (pin "132") (pinfunction "PG15_132") (pintype "passive"))
    )
    (net (code "109") (name "/RESET") (class "Default")
      (node (ref "C13") (pin "2") (pinfunction "2_2") (pintype "passive"))
      (node (ref "JP1") (pin "15") (pinfunction "NSRST_15") (pintype "passive"))
      (node (ref "R13") (pin "1") (pinfunction "1_1") (pintype "passive"))
      (node (ref "RESET") (pin "2") (pinfunction "2_2") (pintype "passive"))
      (node (ref "U1") (pin "25") (pinfunction "NRST_25") (pintype "passive"))
      (node (ref "U2") (pin "40") (pinfunction "PWRST_40") (pintype "passive"))
      (node (ref "U7") (pin "4") (pinfunction "RESET_4") (pintype "passive"))
    )
    (net (code "110") (name "/RX_N") (class "Default")
      (node (ref "CON1") (pin "3") (pinfunction "RD+_3") (pintype "passive"))
      (node (ref "R8") (pin "2") (pinfunction "2_2") (pintype "passive"))
      (node (ref "U2") (pin "3") (pinfunction "RX+_3") (pintype "passive"))
    )
    (net (code "111") (name "/RX_P") (class "Default")
      (node (ref "CON1") (pin "6") (pinfunction "RD-_6") (pintype "passive"))
      (node (ref "R7") (pin "2") (pinfunction "2_2") (pintype "passive"))
      (node (ref "U2") (pin "4") (pinfunction "RX-_4") (pintype "passive"))
    )
    (net (code "112") (name "/TCK") (class "Default")
      (node (ref "JP1") (pin "9") (pinfunction "TCK_9") (pintype "passive"))
      (node (ref "U1") (pin "109") (pinfunction "PA14/JTMS-SWCLK_109") (pintype "passive"))
    )
    (net (code "113") (name "/TDI") (class "Default")
      (node (ref "JP1") (pin "5") (pinfunction "TDI_5") (pintype "passive"))
      (node (ref "U1") (pin "110") (pinfunction "PA15/JTDI/SPI3_NSS/I2S3_WS_110") (pintype "passive"))
    )
    (net (code "114") (name "/TDO") (class "Default")
      (node (ref "JP1") (pin "13") (pinfunction "TDO_13") (pintype "passive"))
      (node (ref "U1") (pin "133") (pinfunction "PB3/JTDO/TRACESWO/SPI3_SCK/I2S3_CK_133") (pintype "passive"))
    )
    (net (code "115") (name "/TMS") (class "Default")
      (node (ref "JP1") (pin "7") (pinfunction "TMS_7") (pintype "passive"))
      (node (ref "U1") (pin "105") (pinfunction "PA13/JTMS-SWDIO_105") (pintype "passive"))
    )
    (net (code "116") (name "/TRST") (class "Default")
      (node (ref "JP1") (pin "3") (pinfunction "NTRST_3") (pintype "passive"))
      (node (ref "U1") (pin "134") (pinfunction "PB4/JNTRST/SPI3_MISO_134") (pintype "passive"))
    )
    (net (code "117") (name "/TX_N") (class "Default")
      (node (ref "CON1") (pin "1") (pinfunction "TD+_1") (pintype "passive"))
      (node (ref "R10") (pin "2") (pinfunction "2_2") (pintype "passive"))
      (node (ref "U2") (pin "7") (pinfunction "TX+_7") (pintype "passive"))
    )
    (net (code "118") (name "/TX_P") (class "Default")
      (node (ref "CON1") (pin "2") (pinfunction "TD-_2") (pintype "passive"))
      (node (ref "R9") (pin "2") (pinfunction "2_2") (pintype "passive"))
      (node (ref "U2") (pin "8") (pinfunction "TX-_8") (pintype "passive"))
    )
    (net (code "119") (name "/USB_DIS") (class "Default")
      (node (ref "R37") (pin "2") (pinfunction "2_2") (pintype "passive"))
      (node (ref "U1") (pin "75") (pinfunction "PB14/SPI2_MISO/USART3_RTS/TIM1_CH2N_75") (pintype "passive"))
    )
    (net (code "120") (name "/USB_DM") (class "Default")
      (node (ref "R43") (pin "2") (pinfunction "2_2") (pintype "passive"))
      (node (ref "U1") (pin "103") (pinfunction "PA11/USART1_CTS/CANRX/TIM1_CH4/USBDM_103") (pintype "passive"))
    )
    (net (code "121") (name "/USB_DP") (class "Default")
      (node (ref "R44") (pin "2") (pinfunction "2_2") (pintype "passive"))
      (node (ref "U1") (pin "104") (pinfunction "PA12/USART1_RTS/CANTX/TIM1_ETR/USBDP_104") (pintype "passive"))
    )
    (net (code "122") (name "3V3") (class "Default")
      (node (ref "C1") (pin "1") (pinfunction "1_1") (pintype "passive"))
      (node (ref "C14") (pin "1") (pinfunction "1_1") (pintype "passive"))
      (node (ref "C15") (pin "1") (pinfunction "1_1") (pintype "passive"))
      (node (ref "C19") (pin "2") (pinfunction "2_2") (pintype "passive"))
      (node (ref "C2") (pin "1") (pinfunction "1_1") (pintype "passive"))
      (node (ref "C23") (pin "1") (pinfunction "1_1") (pintype "passive"))
      (node (ref "C24") (pin "1") (pinfunction "1_1") (pintype "passive"))
      (node (ref "C25") (pin "1") (pinfunction "1_1") (pintype "passive"))
      (node (ref "C26") (pin "1") (pinfunction "1_1") (pintype "passive"))
      (node (ref "C27") (pin "1") (pinfunction "1_1") (pintype "passive"))
      (node (ref "C28") (pin "1") (pinfunction "1_1") (pintype "passive"))
      (node (ref "C29") (pin "1") (pinfunction "1_1") (pintype "passive"))
      (node (ref "C30") (pin "1") (pinfunction "1_1") (pintype "passive"))
      (node (ref "C31") (pin "1") (pinfunction "1_1") (pintype "passive"))
      (node (ref "C32") (pin "1") (pinfunction "1_1") (pintype "passive"))
      (node (ref "C33") (pin "1") (pinfunction "1_1") (pintype "passive"))
      (node (ref "C35") (pin "2") (pinfunction "2_2") (pintype "passive"))
      (node (ref "C39") (pin "1") (pinfunction "1_1") (pintype "passive"))
      (node (ref "C42") (pin "1") (pinfunction "1_1") (pintype "passive"))
      (node (ref "C44") (pin "1") (pinfunction "1_1") (pintype "passive"))
      (node (ref "C45") (pin "1") (pinfunction "1_1") (pintype "passive"))
      (node (ref "C46") (pin "1") (pinfunction "1_1") (pintype "passive"))
      (node (ref "C47") (pin "1") (pinfunction "1_1") (pintype "passive"))
      (node (ref "C50") (pin "1") (pinfunction "1_1") (pintype "passive"))
      (node (ref "C53") (pin "1") (pinfunction "1_1") (pintype "passive"))
      (node (ref "CON2") (pin "1") (pinfunction "1_1") (pintype "passive"))
      (node (ref "CON3") (pin "1") (pinfunction "1_1") (pintype "passive"))
      (node (ref "CON4") (pin "2") (pinfunction "2_2") (pintype "passive"))
      (node (ref "D1") (pin "2") (pinfunction "2_2") (pintype "passive"))
      (node (ref "D3") (pin "1") (pinfunction "1_1") (pintype "passive"))
      (node (ref "D4") (pin "1") (pinfunction "1_1") (pintype "passive"))
      (node (ref "D5") (pin "1") (pinfunction "1_1") (pintype "passive"))
      (node (ref "D6") (pin "1") (pinfunction "1_1") (pintype "passive"))
      (node (ref "D7") (pin "1") (pinfunction "1_1") (pintype "passive"))
      (node (ref "JP1") (pin "1") (pinfunction "VTREF_1") (pintype "passive"))
      (node (ref "JP1") (pin "2") (pinfunction "VS_2") (pintype "passive"))
      (node (ref "JP2") (pin "1") (pinfunction "1_1") (pintype "passive"))
      (node (ref "JP2") (pin "2") (pinfunction "2_2") (pintype "passive"))
      (node (ref "JP5") (pin "4") (pinfunction "VDD_4") (pintype "passive"))
      (node (ref "Q1") (pin "2") (pinfunction "E_2") (pintype "passive"))
      (node (ref "Q2") (pin "2") (pinfunction "E_2") (pintype "passive"))
      (node (ref "R1") (pin "2") (pinfunction "2_2") (pintype "passive"))
      (node (ref "R11") (pin "1") (pinfunction "1_1") (pintype "passive"))
      (node (ref "R12") (pin "1") (pinfunction "1_1") (pintype "passive"))
      (node (ref "R13") (pin "2") (pinfunction "2_2") (pintype "passive"))
      (node (ref "R27") (pin "2") (pinfunction "2_2") (pintype "passive"))
      (node (ref "R28") (pin "2") (pinfunction "2_2") (pintype "passive"))
      (node (ref "R29") (pin "2") (pinfunction "2_2") (pintype "passive"))
      (node (ref "R30") (pin "2") (pinfunction "2_2") (pintype "passive"))
      (node (ref "R31") (pin "2") (pinfunction "2_2") (pintype "passive"))
      (node (ref "R34") (pin "2") (pinfunction "2_2") (pintype "passive"))
      (node (ref "R39") (pin "2") (pinfunction "2_2") (pintype "passive"))
      (node (ref "R40") (pin "2") (pinfunction "2_2") (pintype "passive"))
      (node (ref "R5") (pin "2") (pinfunction "2_2") (pintype "passive"))
      (node (ref "R6") (pin "2") (pinfunction "2_2") (pintype "passive"))
      (node (ref "RV1") (pin "2") (pinfunction "B_2") (pintype "passive"))
      (node (ref "U1") (pin "108") (pinfunction "VDD2_108") (pintype "passive"))
      (node (ref "U1") (pin "121") (pinfunction "VDD10_121") (pintype "passive"))
      (node (ref "U1") (pin "131") (pinfunction "VDD11_131") (pintype "passive"))
      (node (ref "U1") (pin "144") (pinfunction "VDD3_144") (pintype "passive"))
      (node (ref "U1") (pin "17") (pinfunction "VDD5_17") (pintype "passive"))
      (node (ref "U1") (pin "32") (pinfunction "Vref+_32") (pintype "passive"))
      (node (ref "U1") (pin "33") (pinfunction "VDDA_33") (pintype "passive"))
      (node (ref "U1") (pin "39") (pinfunction "VDD4_39") (pintype "passive"))
      (node (ref "U1") (pin "52") (pinfunction "VDD6_52") (pintype "passive"))
      (node (ref "U1") (pin "62") (pinfunction "VDD7_62") (pintype "passive"))
      (node (ref "U1") (pin "72") (pinfunction "VDD1_72") (pintype "passive"))
      (node (ref "U1") (pin "84") (pinfunction "VDD8_84") (pintype "passive"))
      (node (ref "U1") (pin "95") (pinfunction "VDD9_95") (pintype "passive"))
      (node (ref "U10") (pin "8") (pinfunction "VCC_8") (pintype "passive"))
      (node (ref "U11") (pin "16") (pinfunction "VCC_16") (pintype "passive"))
      (node (ref "U12") (pin "3") (pinfunction "VCC_3") (pintype "power_in"))
      (node (ref "U2") (pin "23") (pinfunction "VDD_3_23") (pintype "passive"))
      (node (ref "U2") (pin "30") (pinfunction "VDD_2_30") (pintype "passive"))
      (node (ref "U2") (pin "42") (pinfunction "VDD_1_42") (pintype "passive"))
      (node (ref "U3") (pin "11") (pinfunction "Vhp_11") (pintype "passive"))
      (node (ref "U3") (pin "12") (pinfunction "Vcc_12") (pintype "passive"))
      (node (ref "U4") (pin "3") (pinfunction "VCC_3") (pintype "passive"))
      (node (ref "U6") (pin "3") (pinfunction "~{WP}_3") (pintype "passive"))
      (node (ref "U6") (pin "7") (pinfunction "~{HOLD}_7") (pintype "passive"))
      (node (ref "U6") (pin "8") (pinfunction "VDD_8") (pintype "passive"))
      (node (ref "U8") (pin "11") (pinfunction "VDD_11") (pintype "passive"))
      (node (ref "U8") (pin "33") (pinfunction "VDD_33") (pintype "passive"))
      (node (ref "U9") (pin "2") (pinfunction "VOUT_2") (pintype "passive"))
    )
    (net (code "123") (name "5V") (class "Default")
      (node (ref "C37") (pin "1") (pinfunction "1_1") (pintype "passive"))
      (node (ref "C40") (pin "1") (pinfunction "1_1") (pintype "passive"))
      (node (ref "C43") (pin "1") (pinfunction "1_1") (pintype "passive"))
      (node (ref "CON4") (pin "1") (pinfunction "1_1") (pintype "passive"))
      (node (ref "F1") (pin "2") (pinfunction "2_2") (pintype "passive"))
      (node (ref "U5") (pin "16") (pinfunction "VCC_16") (pintype "passive"))
      (node (ref "U7") (pin "19") (pinfunction "5V_19") (pintype "passive"))
      (node (ref "U9") (pin "3") (pinfunction "VIN_3") (pintype "passive"))
    )
    (net (code "124") (name "ANGND2") (class "Default")
      (node (ref "C3") (pin "2") (pinfunction "2_2") (pintype "passive"))
      (node (ref "C4") (pin "2") (pinfunction "2_2") (pintype "passive"))
      (node (ref "C6") (pin "2") (pinfunction "2_2") (pintype "passive"))
      (node (ref "C7") (pin "2") (pinfunction "2_2") (pintype "passive"))
      (node (ref "R2") (pin "2") (pinfunction "2_2") (pintype "passive"))
      (node (ref "R4") (pin "1") (pinfunction "1_1") (pintype "passive"))
      (node (ref "U2") (pin "47") (pinfunction "AGND_1_47") (pintype "passive"))
      (node (ref "U2") (pin "48") (pinfunction "BGGND_48") (pintype "passive"))
      (node (ref "U2") (pin "5") (pinfunction "AGND_3_5") (pintype "passive"))
      (node (ref "U2") (pin "6") (pinfunction "AGND_2_6") (pintype "passive"))
    )
    (net (code "125") (name "AVDD25") (class "Default")
      (node (ref "C3") (pin "1") (pinfunction "1_1") (pintype "passive"))
      (node (ref "C4") (pin "1") (pinfunction "1_1") (pintype "passive"))
      (node (ref "CON1") (pin "4") (pinfunction "4_4") (pintype "passive"))
      (node (ref "CON1") (pin "5") (pinfunction "5_5") (pintype "passive"))
      (node (ref "U2") (pin "2") (pinfunction "VDD25_2_2") (pintype "passive"))
      (node (ref "U2") (pin "9") (pinfunction "VDD25_1_9") (pintype "passive"))
    )
    (net (code "126") (name "CHASIS") (class "Default")
      (node (ref "CON1") (pin "13") (pinfunction "13_13") (pintype "passive"))
      (node (ref "CON1") (pin "14") (pinfunction "14_14") (pintype "passive"))
      (node (ref "CON1") (pin "8") (pinfunction "CHSGND_8") (pintype "passive"))
      (node (ref "R3") (pin "2") (pinfunction "2_2") (pintype "passive"))
    )
    (net (code "127") (name "GND") (class "Default")
      (node (ref "BAT1") (pin "2") (pinfunction "-_2") (pintype "passive"))
      (node (ref "C1") (pin "2") (pinfunction "2_2") (pintype "passive"))
      (node (ref "C10") (pin "1") (pinfunction "1_1") (pintype "passive"))
      (node (ref "C11") (pin "1") (pinfunction "1_1") (pintype "passive"))
      (node (ref "C12") (pin "2") (pinfunction "2_2") (pintype "passive"))
      (node (ref "C13") (pin "1") (pinfunction "1_1") (pintype "passive"))
      (node (ref "C14") (pin "2") (pinfunction "2_2") (pintype "passive"))
      (node (ref "C15") (pin "2") (pinfunction "2_2") (pintype "passive"))
      (node (ref "C16") (pin "2") (pinfunction "2_2") (pintype "passive"))
      (node (ref "C19") (pin "1") (pinfunction "1_1") (pintype "passive"))
      (node (ref "C2") (pin "2") (pinfunction "2_2") (pintype "passive"))
      (node (ref "C23") (pin "2") (pinfunction "2_2") (pintype "passive"))
      (node (ref "C24") (pin "2") (pinfunction "2_2") (pintype "passive"))
      (node (ref "C25") (pin "2") (pinfunction "2_2") (pintype "passive"))
      (node (ref "C26") (pin "2") (pinfunction "2_2") (pintype "passive"))
      (node (ref "C27") (pin "2") (pinfunction "2_2") (pintype "passive"))
      (node (ref "C28") (pin "2") (pinfunction "2_2") (pintype "passive"))
      (node (ref "C29") (pin "2") (pinfunction "2_2") (pintype "passive"))
      (node (ref "C30") (pin "2") (pinfunction "2_2") (pintype "passive"))
      (node (ref "C31") (pin "2") (pinfunction "2_2") (pintype "passive"))
      (node (ref "C32") (pin "2") (pinfunction "2_2") (pintype "passive"))
      (node (ref "C33") (pin "2") (pinfunction "2_2") (pintype "passive"))
      (node (ref "C34") (pin "2") (pinfunction "2_2") (pintype "passive"))
      (node (ref "C35") (pin "1") (pinfunction "1_1") (pintype "passive"))
      (node (ref "C36") (pin "1") (pinfunction "1_1") (pintype "passive"))
      (node (ref "C37") (pin "2") (pinfunction "2_2") (pintype "passive"))
      (node (ref "C38") (pin "1") (pinfunction "1_1") (pintype "passive"))
      (node (ref "C39") (pin "2") (pinfunction "2_2") (pintype "passive"))
      (node (ref "C40") (pin "2") (pinfunction "2_2") (pintype "passive"))
      (node (ref "C42") (pin "2") (pinfunction "2_2") (pintype "passive"))
      (node (ref "C43") (pin "2") (pinfunction "2_2") (pintype "passive"))
      (node (ref "C44") (pin "2") (pinfunction "2_2") (pintype "passive"))
      (node (ref "C45") (pin "2") (pinfunction "2_2") (pintype "passive"))
      (node (ref "C46") (pin "2") (pinfunction "2_2") (pintype "passive"))
      (node (ref "C47") (pin "2") (pinfunction "2_2") (pintype "passive"))
      (node (ref "C49") (pin "1") (pinfunction "1_1") (pintype "passive"))
      (node (ref "C5") (pin "1") (pinfunction "1_1") (pintype "passive"))
      (node (ref "C50") (pin "2") (pinfunction "2_2") (pintype "passive"))
      (node (ref "C51") (pin "1") (pinfunction "1_1") (pintype "passive"))
      (node (ref "C54") (pin "2") (pinfunction "2_2") (pintype "passive"))
      (node (ref "C8") (pin "2") (pinfunction "2_2") (pintype "passive"))
      (node (ref "C9") (pin "1") (pinfunction "1_1") (pintype "passive"))
      (node (ref "CON2") (pin "2") (pinfunction "2_2") (pintype "passive"))
      (node (ref "CON3") (pin "2") (pinfunction "2_2") (pintype "passive"))
      (node (ref "CON4") (pin "3") (pinfunction "3_3") (pintype "passive"))
      (node (ref "CON4") (pin "5") (pinfunction "5_5") (pintype "passive"))
      (node (ref "J1") (pin "3") (pinfunction "C_3") (pintype "passive"))
      (node (ref "J2") (pin "10") (pinfunction "MH1_10") (pintype "passive"))
      (node (ref "J2") (pin "11") (pinfunction "MH2_11") (pintype "passive"))
      (node (ref "J2") (pin "5") (pinfunction "5_5") (pintype "passive"))
      (node (ref "JP1") (pin "10") (pinfunction "GND_10") (pintype "passive"))
      (node (ref "JP1") (pin "12") (pinfunction "GND_12") (pintype "passive"))
      (node (ref "JP1") (pin "14") (pinfunction "GND_14") (pintype "passive"))
      (node (ref "JP1") (pin "16") (pinfunction "GND_16") (pintype "passive"))
      (node (ref "JP1") (pin "18") (pinfunction "GND_18") (pintype "passive"))
      (node (ref "JP1") (pin "20") (pinfunction "GND_20") (pintype "passive"))
      (node (ref "JP1") (pin "4") (pinfunction "GND_4") (pintype "passive"))
      (node (ref "JP1") (pin "6") (pinfunction "GND_6") (pintype "passive"))
      (node (ref "JP1") (pin "8") (pinfunction "GND_8") (pintype "passive"))
      (node (ref "JP2") (pin "5") (pinfunction "5_5") (pintype "passive"))
      (node (ref "JP2") (pin "6") (pinfunction "6_6") (pintype "passive"))
      (node (ref "JP3") (pin "4") (pinfunction "4_4") (pintype "passive"))
      (node (ref "JP3") (pin "5") (pinfunction "5_5") (pintype "passive"))
      (node (ref "JP4") (pin "5") (pinfunction "GND_5") (pintype "passive"))
      (node (ref "JP4") (pin "6") (pinfunction "S_6") (pintype "passive"))
      (node (ref "JP4") (pin "7") (pinfunction "S_7") (pintype "passive"))
      (node (ref "JP4") (pin "8") (pinfunction "S_8") (pintype "passive"))
      (node (ref "JP5") (pin "10") (pinfunction "GND_10") (pintype "passive"))
      (node (ref "JP5") (pin "6") (pinfunction "VSS_6") (pintype "passive"))
      (node (ref "JP6") (pin "5") (pinfunction "GND_5") (pintype "passive"))
      (node (ref "JP6") (pin "6") (pinfunction "S_6") (pintype "passive"))
      (node (ref "JP6") (pin "7") (pinfunction "S_7") (pintype "passive"))
      (node (ref "JP6") (pin "8") (pinfunction "S_8") (pintype "passive"))
      (node (ref "KEY1") (pin "1") (pinfunction "1_1") (pintype "passive"))
      (node (ref "KEY2") (pin "1") (pinfunction "1_1") (pintype "passive"))
      (node (ref "KEY3") (pin "1") (pinfunction "1_1") (pintype "passive"))
      (node (ref "KEY4") (pin "1") (pinfunction "1_1") (pintype "passive"))
      (node (ref "KEY5") (pin "1") (pinfunction "1_1") (pintype "passive"))
      (node (ref "R19") (pin "1") (pinfunction "1_1") (pintype "passive"))
      (node (ref "R2") (pin "1") (pinfunction "1_1") (pintype "passive"))
      (node (ref "R20") (pin "1") (pinfunction "1_1") (pintype "passive"))
      (node (ref "R3") (pin "1") (pinfunction "1_1") (pintype "passive"))
      (node (ref "R32") (pin "2") (pinfunction "2_2") (pintype "passive"))
      (node (ref "R42") (pin "1") (pinfunction "1_1") (pintype "passive"))
      (node (ref "RESET") (pin "1") (pinfunction "1_1") (pintype "passive"))
      (node (ref "RV1") (pin "1") (pinfunction "A_1") (pintype "passive"))
      (node (ref "U1") (pin "107") (pinfunction "VSS2_107") (pintype "passive"))
      (node (ref "U1") (pin "120") (pinfunction "VSS10_120") (pintype "passive"))
      (node (ref "U1") (pin "130") (pinfunction "VSS11_130") (pintype "passive"))
      (node (ref "U1") (pin "143") (pinfunction "VSS3_143") (pintype "passive"))
      (node (ref "U1") (pin "16") (pinfunction "VSS5_16") (pintype "passive"))
      (node (ref "U1") (pin "30") (pinfunction "VSSA_30") (pintype "passive"))
      (node (ref "U1") (pin "31") (pinfunction "Vref-_31") (pintype "passive"))
      (node (ref "U1") (pin "38") (pinfunction "VSS4_38") (pintype "passive"))
      (node (ref "U1") (pin "51") (pinfunction "VSS6_51") (pintype "passive"))
      (node (ref "U1") (pin "61") (pinfunction "VSS7_61") (pintype "passive"))
      (node (ref "U1") (pin "71") (pinfunction "VSS1_71") (pintype "passive"))
      (node (ref "U1") (pin "83") (pinfunction "VSS8_83") (pintype "passive"))
      (node (ref "U1") (pin "94") (pinfunction "VSS9_94") (pintype "passive"))
      (node (ref "U10") (pin "1") (pinfunction "A0_1") (pintype "passive"))
      (node (ref "U10") (pin "2") (pinfunction "A1_2") (pintype "passive"))
      (node (ref "U10") (pin "3") (pinfunction "A2_3") (pintype "passive"))
      (node (ref "U10") (pin "4") (pinfunction "GND_4") (pintype "passive"))
      (node (ref "U10") (pin "7") (pinfunction "WP_7") (pintype "passive"))
      (node (ref "U11") (pin "15") (pinfunction "GND_15") (pintype "passive"))
      (node (ref "U2") (pin "15") (pinfunction "GND_3_15") (pintype "passive"))
      (node (ref "U2") (pin "33") (pinfunction "GND_2_33") (pintype "passive"))
      (node (ref "U2") (pin "41") (pinfunction "TEST_41") (pintype "passive"))
      (node (ref "U2") (pin "45") (pinfunction "GND_1_45") (pintype "passive"))
      (node (ref "U3") (pin "5") (pinfunction "AGND_5") (pintype "passive"))
      (node (ref "U3") (pin "6") (pinfunction "HGND_6") (pintype "passive"))
      (node (ref "U4") (pin "2") (pinfunction "GND_2") (pintype "passive"))
      (node (ref "U5") (pin "1") (pinfunction "GND_1") (pintype "passive"))
      (node (ref "U6") (pin "4") (pinfunction "GND_4") (pintype "passive"))
      (node (ref "U7") (pin "20") (pinfunction "GND_20") (pintype "passive"))
      (node (ref "U8") (pin "12") (pinfunction "GND_12") (pintype "passive"))
      (node (ref "U8") (pin "34") (pinfunction "GND_34") (pintype "passive"))
      (node (ref "U9") (pin "1") (pinfunction "GND_1") (pintype "passive"))
    )
    (net (code "128") (name "Net-(BAT1-+)") (class "Default")
      (node (ref "BAT1") (pin "1") (pinfunction "+_1") (pintype "passive"))
      (node (ref "D1") (pin "1") (pinfunction "1_1") (pintype "passive"))
    )
    (net (code "129") (name "Net-(C6-Pad1)") (class "Default")
      (node (ref "C6") (pin "1") (pinfunction "1_1") (pintype "passive"))
      (node (ref "R7") (pin "1") (pinfunction "1_1") (pintype "passive"))
      (node (ref "R8") (pin "1") (pinfunction "1_1") (pintype "passive"))
    )
    (net (code "130") (name "Net-(C7-Pad1)") (class "Default")
      (node (ref "C7") (pin "1") (pinfunction "1_1") (pintype "passive"))
      (node (ref "R10") (pin "1") (pinfunction "1_1") (pintype "passive"))
      (node (ref "R9") (pin "1") (pinfunction "1_1") (pintype "passive"))
    )
    (net (code "131") (name "Net-(C20-Pad2)") (class "Default")
      (node (ref "C20") (pin "2") (pinfunction "2_2") (pintype "passive"))
      (node (ref "R19") (pin "2") (pinfunction "2_2") (pintype "passive"))
    )
    (net (code "132") (name "Net-(C22-Pad2)") (class "Default")
      (node (ref "C22") (pin "2") (pinfunction "2_2") (pintype "passive"))
      (node (ref "R20") (pin "2") (pinfunction "2_2") (pintype "passive"))
    )
    (net (code "133") (name "Net-(CON1-LED1+)") (class "Default")
      (node (ref "CON1") (pin "9") (pinfunction "LED1+_9") (pintype "passive"))
      (node (ref "R11") (pin "2") (pinfunction "2_2") (pintype "passive"))
    )
    (net (code "134") (name "Net-(CON1-LED2+)") (class "Default")
      (node (ref "CON1") (pin "12") (pinfunction "LED2+_12") (pintype "passive"))
      (node (ref "R12") (pin "2") (pinfunction "2_2") (pintype "passive"))
    )
    (net (code "135") (name "Net-(D3-Pad2)") (class "Default")
      (node (ref "D3") (pin "2") (pinfunction "2_2") (pintype "passive"))
      (node (ref "R14") (pin "1") (pinfunction "1_1") (pintype "passive"))
    )
    (net (code "136") (name "Net-(D4-Pad2)") (class "Default")
      (node (ref "D4") (pin "2") (pinfunction "2_2") (pintype "passive"))
      (node (ref "R15") (pin "1") (pinfunction "1_1") (pintype "passive"))
    )
    (net (code "137") (name "Net-(D5-Pad2)") (class "Default")
      (node (ref "D5") (pin "2") (pinfunction "2_2") (pintype "passive"))
      (node (ref "R16") (pin "1") (pinfunction "1_1") (pintype "passive"))
    )
    (net (code "138") (name "Net-(D6-Pad2)") (class "Default")
      (node (ref "D6") (pin "2") (pinfunction "2_2") (pintype "passive"))
      (node (ref "R18") (pin "1") (pinfunction "1_1") (pintype "passive"))
    )
    (net (code "139") (name "Net-(D7-Pad2)") (class "Default")
      (node (ref "D7") (pin "2") (pinfunction "2_2") (pintype "passive"))
      (node (ref "R32") (pin "1") (pinfunction "1_1") (pintype "passive"))
    )
    (net (code "140") (name "Net-(F1-Pad1)") (class "Default")
      (node (ref "F1") (pin "1") (pinfunction "1_1") (pintype "passive"))
      (node (ref "JP3") (pin "3") (pinfunction "3_3") (pintype "passive"))
    )
    (net (code "141") (name "Net-(J1-A)") (class "Default")
      (node (ref "C21") (pin "2") (pinfunction "2_2") (pintype "passive"))
      (node (ref "J1") (pin "1") (pinfunction "A_1") (pintype "passive"))
    )
    (net (code "142") (name "Net-(J1-B)") (class "Default")
      (node (ref "C18") (pin "2") (pinfunction "2_2") (pintype "passive"))
      (node (ref "J1") (pin "2") (pinfunction "B_2") (pintype "passive"))
    )
    (net (code "143") (name "Net-(JP2-Pad3)") (class "Default")
      (node (ref "JP2") (pin "3") (pinfunction "3_3") (pintype "passive"))
      (node (ref "R21") (pin "2") (pinfunction "2_2") (pintype "passive"))
    )
    (net (code "144") (name "Net-(JP2-Pad4)") (class "Default")
      (node (ref "JP2") (pin "4") (pinfunction "4_4") (pintype "passive"))
      (node (ref "R22") (pin "1") (pinfunction "1_1") (pintype "passive"))
    )
    (net (code "145") (name "Net-(JP4-D+)") (class "Default")
      (node (ref "JP4") (pin "3") (pinfunction "D+_3") (pintype "passive"))
      (node (ref "R35") (pin "1") (pinfunction "1_1") (pintype "passive"))
      (node (ref "R44") (pin "1") (pinfunction "1_1") (pintype "passive"))
    )
    (net (code "146") (name "Net-(JP4-D-)") (class "Default")
      (node (ref "JP4") (pin "2") (pinfunction "D-_2") (pintype "passive"))
      (node (ref "R43") (pin "1") (pinfunction "1_1") (pintype "passive"))
    )
    (net (code "147") (name "Net-(JP4-VDD)") (class "Default")
      (node (ref "JP3") (pin "2") (pinfunction "2_2") (pintype "passive"))
      (node (ref "JP4") (pin "1") (pinfunction "VDD_1") (pintype "passive"))
      (node (ref "JP6") (pin "1") (pinfunction "VDD_1") (pintype "passive"))
    )
    (net (code "148") (name "Net-(Q1-B)") (class "Default")
      (node (ref "Q1") (pin "1") (pinfunction "B_1") (pintype "passive"))
      (node (ref "R37") (pin "1") (pinfunction "1_1") (pintype "passive"))
    )
    (net (code "149") (name "Net-(Q1-C)") (class "Default")
      (node (ref "Q1") (pin "3") (pinfunction "C_3") (pintype "passive"))
      (node (ref "R35") (pin "2") (pinfunction "2_2") (pintype "passive"))
    )
    (net (code "150") (name "Net-(Q2-B)") (class "Default")
      (node (ref "Q2") (pin "1") (pinfunction "B_1") (pintype "passive"))
      (node (ref "R38") (pin "1") (pinfunction "1_1") (pintype "passive"))
    )
    (net (code "151") (name "Net-(Q2-C)") (class "Default")
      (node (ref "Q2") (pin "3") (pinfunction "C_3") (pintype "passive"))
      (node (ref "R36") (pin "2") (pinfunction "2_2") (pintype "passive"))
      (node (ref "R45") (pin "2") (pinfunction "2_2") (pintype "passive"))
    )
    (net (code "152") (name "Net-(U1-OSC_IN)") (class "Default")
      (node (ref "C10") (pin "2") (pinfunction "2_2") (pintype "passive"))
      (node (ref "U1") (pin "23") (pinfunction "OSC_IN_23") (pintype "passive"))
      (node (ref "Y3") (pin "2") (pinfunction "2_2") (pintype "passive"))
    )
    (net (code "153") (name "Net-(U1-OSC_OUT)") (class "Default")
      (node (ref "C12") (pin "1") (pinfunction "1_1") (pintype "passive"))
      (node (ref "U1") (pin "24") (pinfunction "OSC_OUT_24") (pintype "passive"))
      (node (ref "Y3") (pin "1") (pinfunction "1_1") (pintype "passive"))
    )
    (net (code "154") (name "Net-(U1-PC14-OSC32_IN)") (class "Default")
      (node (ref "C9") (pin "2") (pinfunction "2_2") (pintype "passive"))
      (node (ref "U1") (pin "8") (pinfunction "PC14-OSC32_IN_8") (pintype "passive"))
      (node (ref "Y2") (pin "1") (pinfunction "1_1") (pintype "passive"))
    )
    (net (code "155") (name "Net-(U1-PC15-OSC32_OUT)") (class "Default")
      (node (ref "C11") (pin "2") (pinfunction "2_2") (pintype "passive"))
      (node (ref "U1") (pin "9") (pinfunction "PC15-OSC32_OUT_9") (pintype "passive"))
      (node (ref "Y2") (pin "2") (pinfunction "2_2") (pintype "passive"))
    )
    (net (code "156") (name "Net-(U1-VBAT)") (class "Default")
      (node (ref "D1") (pin "3") (pinfunction "3_3") (pintype "passive"))
      (node (ref "U1") (pin "6") (pinfunction "VBAT_6") (pintype "passive"))
    )
    (net (code "157") (name "Net-(U2-BGRES)") (class "Default")
      (node (ref "R4") (pin "2") (pinfunction "2_2") (pintype "passive"))
      (node (ref "U2") (pin "1") (pinfunction "BGRES_1") (pintype "passive"))
    )
    (net (code "158") (name "Net-(U2-EECK)") (class "Default")
      (node (ref "R6") (pin "1") (pinfunction "1_1") (pintype "passive"))
      (node (ref "U2") (pin "20") (pinfunction "EECK_20") (pintype "passive"))
    )
    (net (code "159") (name "Net-(U2-X1)") (class "Default")
      (node (ref "C5") (pin "2") (pinfunction "2_2") (pintype "passive"))
      (node (ref "U2") (pin "44") (pinfunction "X1_44") (pintype "passive"))
      (node (ref "Y1") (pin "2") (pinfunction "2_2") (pintype "passive"))
    )
    (net (code "160") (name "Net-(U2-X2)") (class "Default")
      (node (ref "C8") (pin "1") (pinfunction "1_1") (pintype "passive"))
      (node (ref "U2") (pin "43") (pinfunction "X2_43") (pintype "passive"))
      (node (ref "Y1") (pin "1") (pinfunction "1_1") (pintype "passive"))
    )
    (net (code "161") (name "Net-(U3-HoutL)") (class "Default")
      (node (ref "C21") (pin "1") (pinfunction "1_1") (pintype "passive"))
      (node (ref "C22") (pin "1") (pinfunction "1_1") (pintype "passive"))
      (node (ref "U3") (pin "9") (pinfunction "HoutL_9") (pintype "passive"))
    )
    (net (code "162") (name "Net-(U3-HoutR)") (class "Default")
      (node (ref "C18") (pin "1") (pinfunction "1_1") (pintype "passive"))
      (node (ref "C20") (pin "1") (pinfunction "1_1") (pintype "passive"))
      (node (ref "U3") (pin "8") (pinfunction "HoutR_8") (pintype "passive"))
    )
    (net (code "163") (name "Net-(U3-Vcom)") (class "Default")
      (node (ref "C16") (pin "1") (pinfunction "1_1") (pintype "passive"))
      (node (ref "U3") (pin "7") (pinfunction "Vcom_7") (pintype "passive"))
    )
    (net (code "164") (name "Net-(U4-OUT)") (class "Default")
      (node (ref "R17") (pin "2") (pinfunction "2_2") (pintype "passive"))
      (node (ref "U4") (pin "1") (pinfunction "OUT_1") (pintype "passive"))
    )
    (net (code "165") (name "Net-(U5-D+)") (class "Default")
      (node (ref "R24") (pin "1") (pinfunction "1_1") (pintype "passive"))
      (node (ref "U5") (pin "5") (pinfunction "D+_5") (pintype "passive"))
    )
    (net (code "166") (name "Net-(U5-D-)") (class "Default")
      (node (ref "R25") (pin "1") (pinfunction "1_1") (pintype "passive"))
      (node (ref "U5") (pin "6") (pinfunction "D-_6") (pintype "passive"))
    )
    (net (code "167") (name "Net-(U5-V3)") (class "Default")
      (node (ref "C36") (pin "2") (pinfunction "2_2") (pintype "passive"))
      (node (ref "U5") (pin "4") (pinfunction "V3_4") (pintype "passive"))
    )
    (net (code "168") (name "Net-(U5-XI)") (class "Default")
      (node (ref "C38") (pin "2") (pinfunction "2_2") (pintype "passive"))
      (node (ref "U5") (pin "7") (pinfunction "XI_7") (pintype "passive"))
      (node (ref "Y4") (pin "1") (pinfunction "1_1") (pintype "passive"))
    )
    (net (code "169") (name "Net-(U5-XO)") (class "Default")
      (node (ref "C34") (pin "1") (pinfunction "1_1") (pintype "passive"))
      (node (ref "U5") (pin "8") (pinfunction "XO_8") (pintype "passive"))
      (node (ref "Y4") (pin "2") (pinfunction "2_2") (pintype "passive"))
    )
    (net (code "170") (name "Net-(U7-LEDA)") (class "Default")
      (node (ref "R36") (pin "1") (pinfunction "1_1") (pintype "passive"))
      (node (ref "R45") (pin "1") (pinfunction "1_1") (pintype "passive"))
      (node (ref "U7") (pin "2") (pinfunction "LEDA_2") (pintype "passive"))
    )
    (net (code "171") (name "Net-(U11-C1+)") (class "Default")
      (node (ref "C48") (pin "2") (pinfunction "2_2") (pintype "passive"))
      (node (ref "U11") (pin "1") (pinfunction "C1+_1") (pintype "passive"))
    )
    (net (code "172") (name "Net-(U11-C1-)") (class "Default")
      (node (ref "C48") (pin "1") (pinfunction "1_1") (pintype "passive"))
      (node (ref "U11") (pin "3") (pinfunction "C1-_3") (pintype "passive"))
    )
    (net (code "173") (name "Net-(U11-C2+)") (class "Default")
      (node (ref "C52") (pin "2") (pinfunction "2_2") (pintype "passive"))
      (node (ref "U11") (pin "4") (pinfunction "C2+_4") (pintype "passive"))
    )
    (net (code "174") (name "Net-(U11-C2-)") (class "Default")
      (node (ref "C52") (pin "1") (pinfunction "1_1") (pintype "passive"))
      (node (ref "U11") (pin "5") (pinfunction "C2-_5") (pintype "passive"))
    )
    (net (code "175") (name "Net-(U11-DOUT1)") (class "Default")
      (node (ref "J2") (pin "2") (pinfunction "2_2") (pintype "passive"))
      (node (ref "U11") (pin "14") (pinfunction "DOUT1_14") (pintype "passive"))
    )
    (net (code "176") (name "Net-(U11-RIN1)") (class "Default")
      (node (ref "J2") (pin "3") (pinfunction "3_3") (pintype "passive"))
      (node (ref "U11") (pin "13") (pinfunction "RIN1_13") (pintype "passive"))
    )
    (net (code "177") (name "Net-(U11-V+)") (class "Default")
      (node (ref "C49") (pin "2") (pinfunction "2_2") (pintype "passive"))
      (node (ref "U11") (pin "2") (pinfunction "V+_2") (pintype "passive"))
    )
    (net (code "178") (name "Net-(U11-V-)") (class "Default")
      (node (ref "C51") (pin "2") (pinfunction "2_2") (pintype "passive"))
      (node (ref "U11") (pin "6") (pinfunction "V-_6") (pintype "passive"))
    )
    (net (code "179") (name "Net-(U12-CANH)") (class "Default")
      (node (ref "JP8") (pin "1") (pinfunction "1_1") (pintype "passive"))
      (node (ref "R41") (pin "2") (pinfunction "2_2") (pintype "passive"))
      (node (ref "U12") (pin "7") (pinfunction "CANH_7") (pintype "passive"))
    )
    (net (code "180") (name "Net-(U12-CANL)") (class "Default")
      (node (ref "JP8") (pin "2") (pinfunction "2_2") (pintype "passive"))
      (node (ref "R41") (pin "1") (pinfunction "1_1") (pintype "passive"))
      (node (ref "U12") (pin "6") (pinfunction "CANL_6") (pintype "passive"))
    )
    (net (code "181") (name "Net-(U12-GND)") (class "Default")
      (node (ref "C53") (pin "2") (pinfunction "2_2") (pintype "passive"))
      (node (ref "U12") (pin "2") (pinfunction "GND_2") (pintype "passive"))
    )
    (net (code "182") (name "Net-(U12-Rs)") (class "Default")
      (node (ref "R42") (pin "2") (pinfunction "2_2") (pintype "passive"))
      (node (ref "U12") (pin "8") (pinfunction "Rs_8") (pintype "passive"))
    )
    (net (code "183") (name "unconnected-(CON1-NC-Pad7)") (class "Default")
      (node (ref "CON1") (pin "7") (pinfunction "NC_7") (pintype "passive"))
    )
    (net (code "184") (name "unconnected-(J2-Pad1)") (class "Default")
      (node (ref "J2") (pin "1") (pinfunction "1_1") (pintype "passive"))
    )
    (net (code "185") (name "unconnected-(J2-Pad4)") (class "Default")
      (node (ref "J2") (pin "4") (pinfunction "4_4") (pintype "passive"))
    )
    (net (code "186") (name "unconnected-(J2-Pad6)") (class "Default")
      (node (ref "J2") (pin "6") (pinfunction "6_6") (pintype "passive"))
    )
    (net (code "187") (name "unconnected-(J2-Pad7)") (class "Default")
      (node (ref "J2") (pin "7") (pinfunction "7_7") (pintype "passive"))
    )
    (net (code "188") (name "unconnected-(J2-Pad8)") (class "Default")
      (node (ref "J2") (pin "8") (pinfunction "8_8") (pintype "passive"))
    )
    (net (code "189") (name "unconnected-(J2-Pad9)") (class "Default")
      (node (ref "J2") (pin "9") (pinfunction "9_9") (pintype "passive"))
    )
    (net (code "190") (name "unconnected-(JP1-DBGACK-Pad19)") (class "Default")
      (node (ref "JP1") (pin "19") (pinfunction "DBGACK_19") (pintype "passive"))
    )
    (net (code "191") (name "unconnected-(JP1-DBGRQ-Pad17)") (class "Default")
      (node (ref "JP1") (pin "17") (pinfunction "DBGRQ_17") (pintype "passive"))
    )
    (net (code "192") (name "unconnected-(JP1-RTCK-Pad11)") (class "Default")
      (node (ref "JP1") (pin "11") (pinfunction "RTCK_11") (pintype "passive"))
    )
    (net (code "193") (name "unconnected-(JP3-Pad1)") (class "Default")
      (node (ref "JP3") (pin "1") (pinfunction "1_1") (pintype "passive"))
    )
    (net (code "194") (name "unconnected-(JP4-ID-Pad4)") (class "Default")
      (node (ref "JP4") (pin "4") (pinfunction "ID_4") (pintype "passive"))
    )
    (net (code "195") (name "unconnected-(JP6-ID-Pad4)") (class "Default")
      (node (ref "JP6") (pin "4") (pinfunction "ID_4") (pintype "passive"))
    )
    (net (code "196") (name "unconnected-(MK1-MARK-Pad1)") (class "Default")
      (node (ref "MK1") (pin "1") (pinfunction "MARK_1") (pintype "passive"))
    )
    (net (code "197") (name "unconnected-(MK2-MARK-Pad1)") (class "Default")
      (node (ref "MK2") (pin "1") (pinfunction "MARK_1") (pintype "passive"))
    )
    (net (code "198") (name "unconnected-(MK3-MARK-Pad1)") (class "Default")
      (node (ref "MK3") (pin "1") (pinfunction "MARK_1") (pintype "passive"))
    )
    (net (code "199") (name "unconnected-(U1-NC-Pad106)") (class "Default")
      (node (ref "U1") (pin "106") (pinfunction "NC_106") (pintype "passive"))
    )
    (net (code "200") (name "unconnected-(U2-EECS-Pad21)") (class "Default")
      (node (ref "U2") (pin "21") (pinfunction "EECS_21") (pintype "passive"))
    )
    (net (code "201") (name "unconnected-(U2-EEDIO-Pad19)") (class "Default")
      (node (ref "U2") (pin "19") (pinfunction "EEDIO_19") (pintype "passive"))
    )
    (net (code "202") (name "unconnected-(U2-SD-Pad46)") (class "Default")
      (node (ref "U2") (pin "46") (pinfunction "SD_46") (pintype "passive"))
    )
    (net (code "203") (name "unconnected-(U3-AIN-Pad10)") (class "Default")
      (node (ref "U3") (pin "10") (pinfunction "AIN_10") (pintype "passive"))
    )
    (net (code "204") (name "unconnected-(U5-CTS-Pad9)") (class "Default")
      (node (ref "U5") (pin "9") (pinfunction "CTS_9") (pintype "passive"))
    )
    (net (code "205") (name "unconnected-(U5-DCD-Pad12)") (class "Default")
      (node (ref "U5") (pin "12") (pinfunction "DCD_12") (pintype "passive"))
    )
    (net (code "206") (name "unconnected-(U5-DSR-Pad10)") (class "Default")
      (node (ref "U5") (pin "10") (pinfunction "DSR_10") (pintype "passive"))
    )
    (net (code "207") (name "unconnected-(U5-DTS-Pad13)") (class "Default")
      (node (ref "U5") (pin "13") (pinfunction "DTS_13") (pintype "passive"))
    )
    (net (code "208") (name "unconnected-(U5-R232-Pad15)") (class "Default")
      (node (ref "U5") (pin "15") (pinfunction "R232_15") (pintype "passive"))
    )
    (net (code "209") (name "unconnected-(U5-RI-Pad11)") (class "Default")
      (node (ref "U5") (pin "11") (pinfunction "RI_11") (pintype "passive"))
    )
    (net (code "210") (name "unconnected-(U5-RTS-Pad14)") (class "Default")
      (node (ref "U5") (pin "14") (pinfunction "RTS_14") (pintype "passive"))
    )
    (net (code "211") (name "unconnected-(U7-NC-Pad1)") (class "Default")
      (node (ref "U7") (pin "1") (pinfunction "NC_1") (pintype "passive"))
    )
    (net (code "212") (name "unconnected-(U7-NC-Pad3)") (class "Default")
      (node (ref "U7") (pin "3") (pinfunction "NC_3") (pintype "passive"))
    )
    (net (code "213") (name "unconnected-(U7-NC-Pad5)") (class "Default")
      (node (ref "U7") (pin "5") (pinfunction "NC_5") (pintype "passive"))
    )
    (net (code "214") (name "unconnected-(U7-NC-Pad18)") (class "Default")
      (node (ref "U7") (pin "18") (pinfunction "NC_18") (pintype "passive"))
    )
    (net (code "215") (name "unconnected-(U7-NC-Pad39)") (class "Default")
      (node (ref "U7") (pin "39") (pinfunction "NC_39") (pintype "passive"))
    )
    (net (code "216") (name "unconnected-(U7-NC-Pad40)") (class "Default")
      (node (ref "U7") (pin "40") (pinfunction "NC_40") (pintype "passive"))
    )
    (net (code "217") (name "unconnected-(U7-SD_CLK-Pad36)") (class "Default")
      (node (ref "U7") (pin "36") (pinfunction "SD_CLK_36") (pintype "passive"))
    )
    (net (code "218") (name "unconnected-(U7-SD_CS-Pad38)") (class "Default")
      (node (ref "U7") (pin "38") (pinfunction "SD_CS_38") (pintype "passive"))
    )
    (net (code "219") (name "unconnected-(U7-SD_MISO-Pad35)") (class "Default")
      (node (ref "U7") (pin "35") (pinfunction "SD_MISO_35") (pintype "passive"))
    )
    (net (code "220") (name "unconnected-(U7-SD_MOSI-Pad37)") (class "Default")
      (node (ref "U7") (pin "37") (pinfunction "SD_MOSI_37") (pintype "passive"))
    )
    (net (code "221") (name "unconnected-(U11-DIN2-Pad10)") (class "Default")
      (node (ref "U11") (pin "10") (pinfunction "DIN2_10") (pintype "passive"))
    )
    (net (code "222") (name "unconnected-(U11-DOUT2-Pad7)") (class "Default")
      (node (ref "U11") (pin "7") (pinfunction "DOUT2_7") (pintype "passive"))
    )
    (net (code "223") (name "unconnected-(U11-RIN2-Pad8)") (class "Default")
      (node (ref "U11") (pin "8") (pinfunction "RIN2_8") (pintype "passive"))
    )
    (net (code "224") (name "unconnected-(U11-ROUT2-Pad9)") (class "Default")
      (node (ref "U11") (pin "9") (pinfunction "ROUT2_9") (pintype "passive"))
    )
    (net (code "225") (name "unconnected-(U12-Verf-Pad5)") (class "Default")
      (node (ref "U12") (pin "5") (pinfunction "Verf_5") (pintype "passive"))
    )
  )
)
